# Roland_mem1.net
KiCad netlist of a schematic drawn in EAGLE
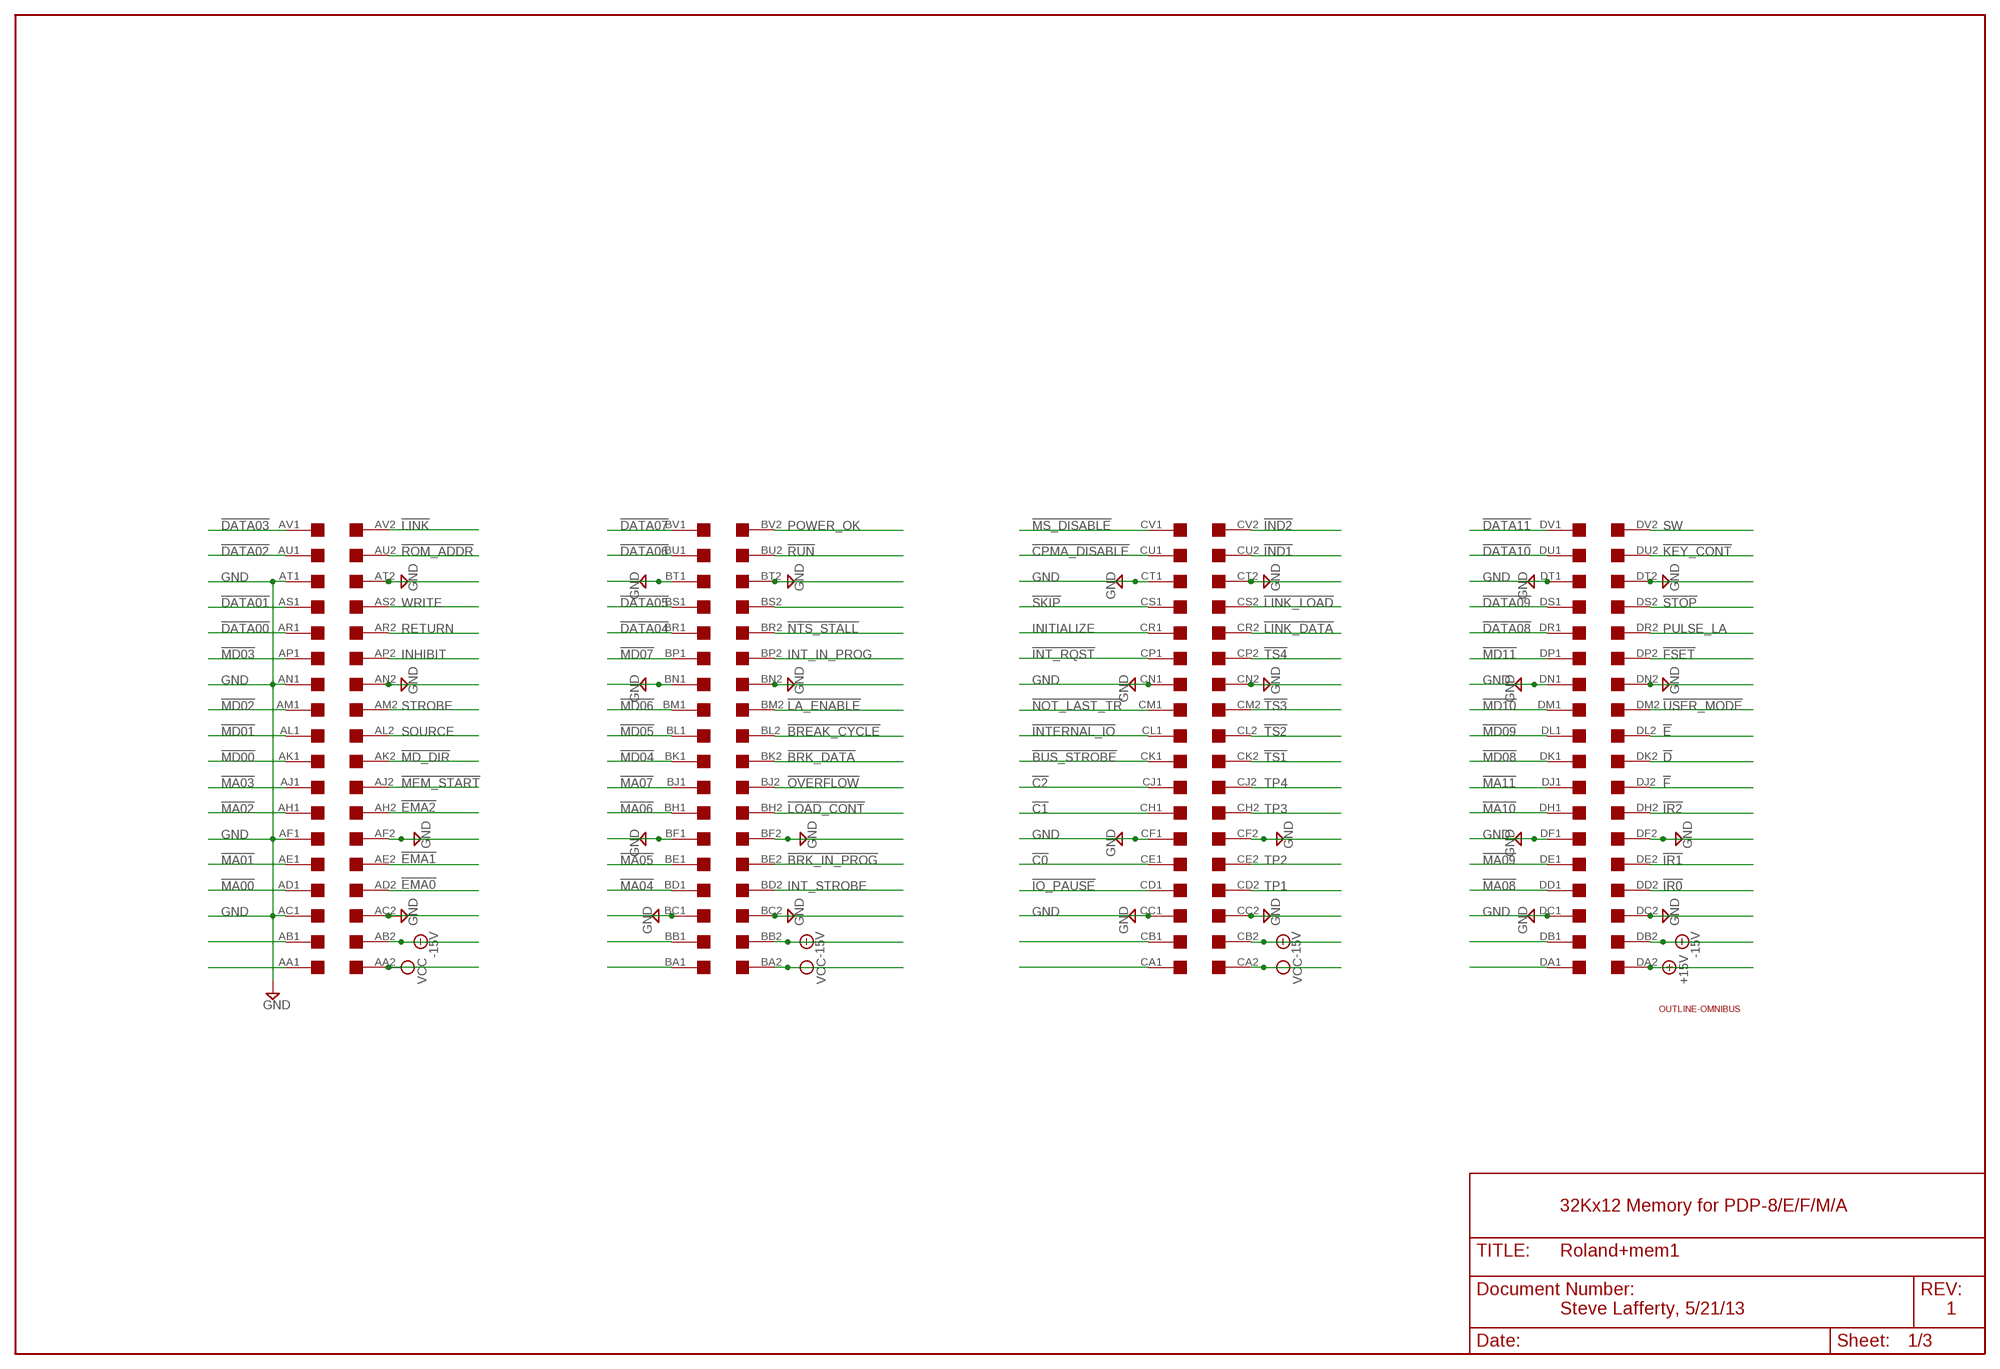
[diagram p0: schematic, sheet 1]
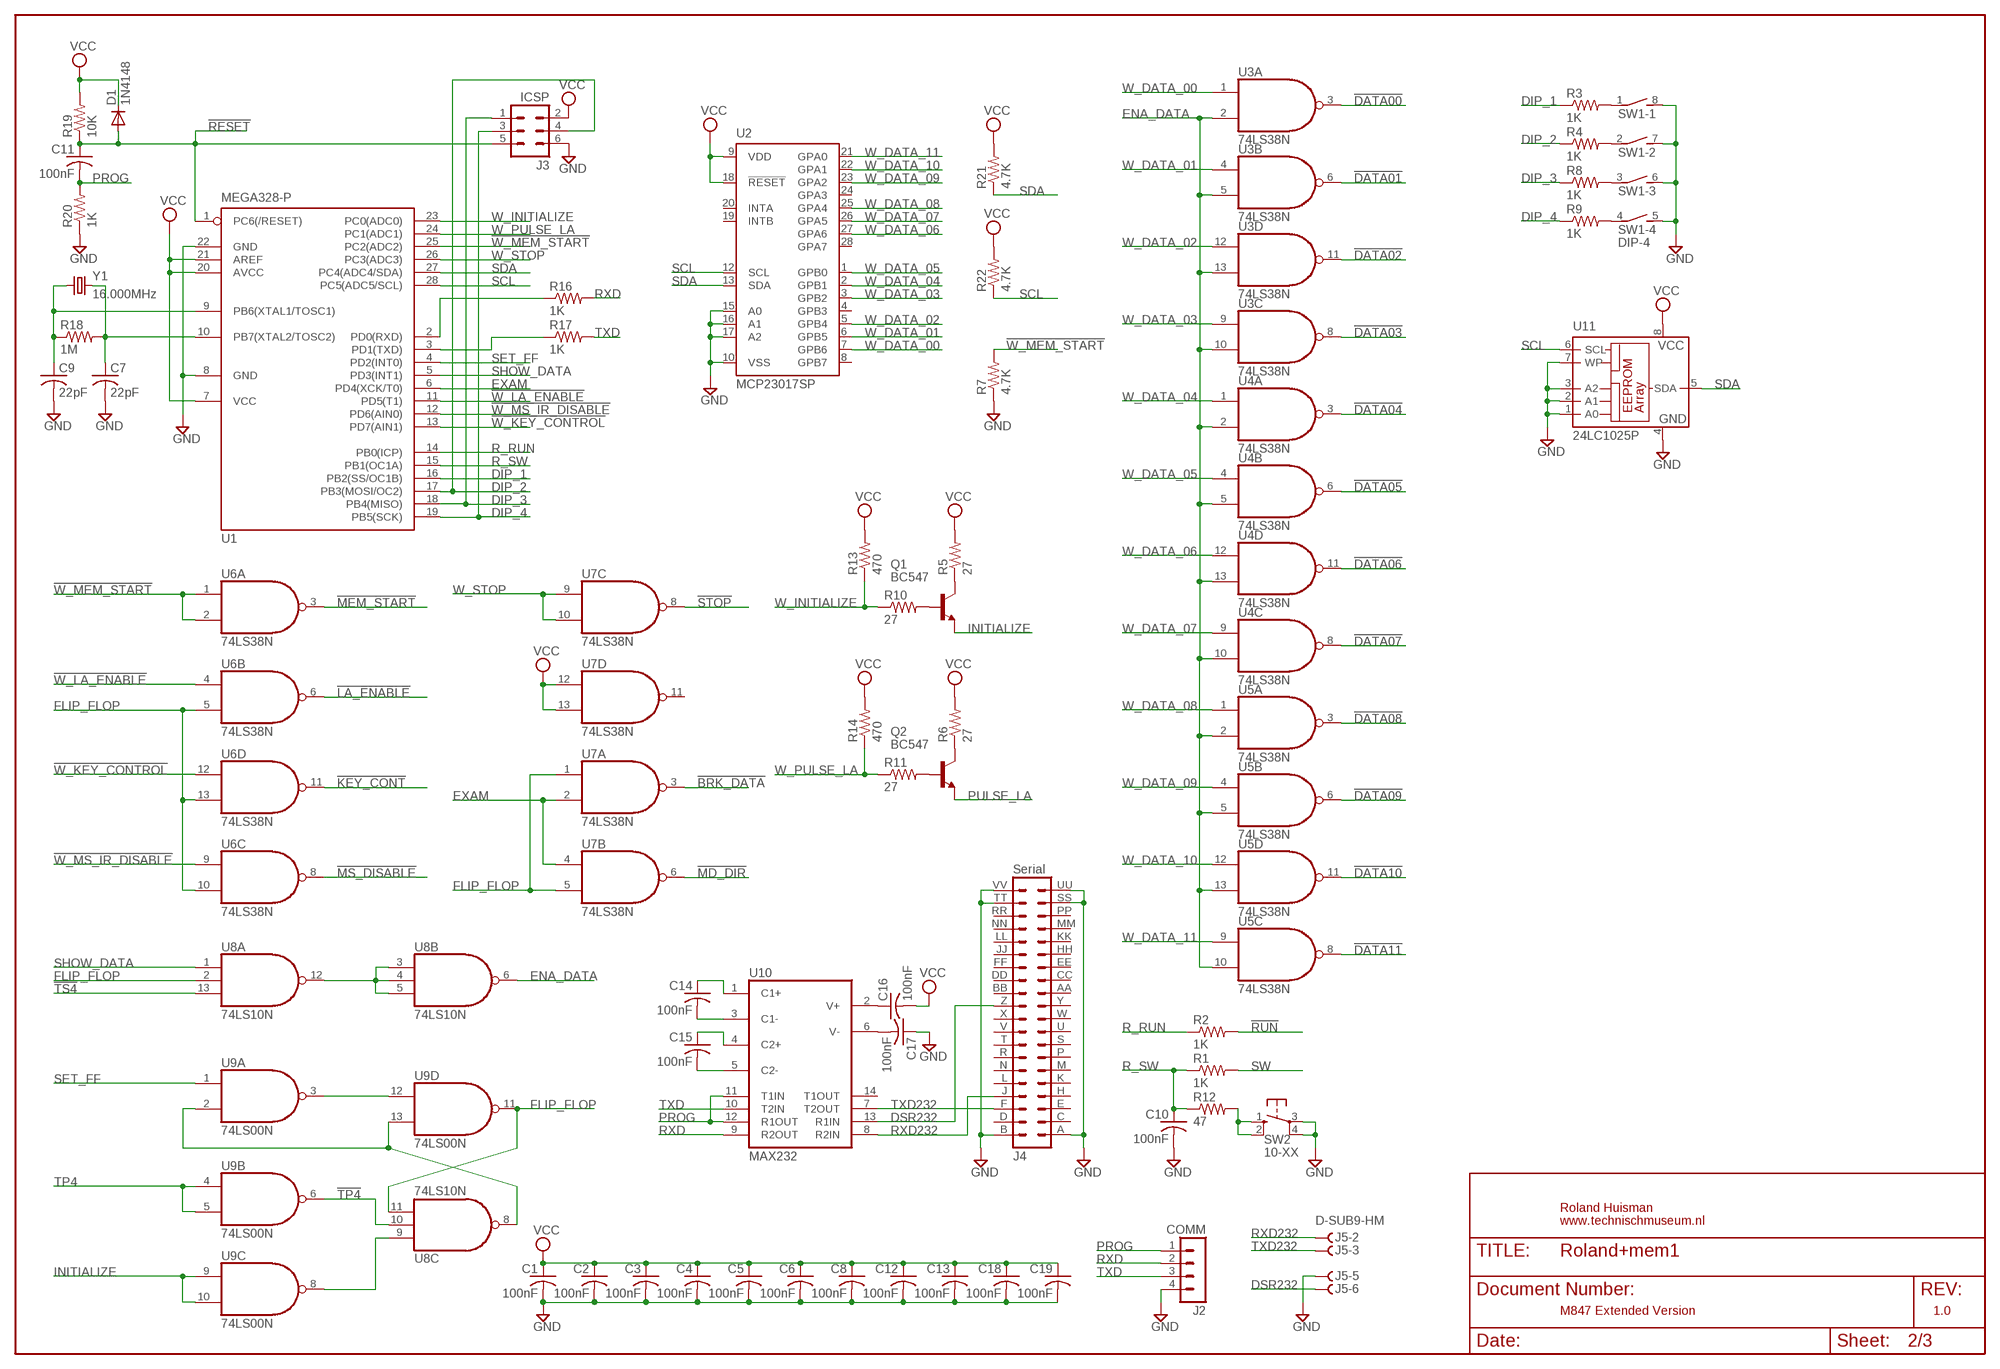
[diagram p1: schematic, sheet 2]
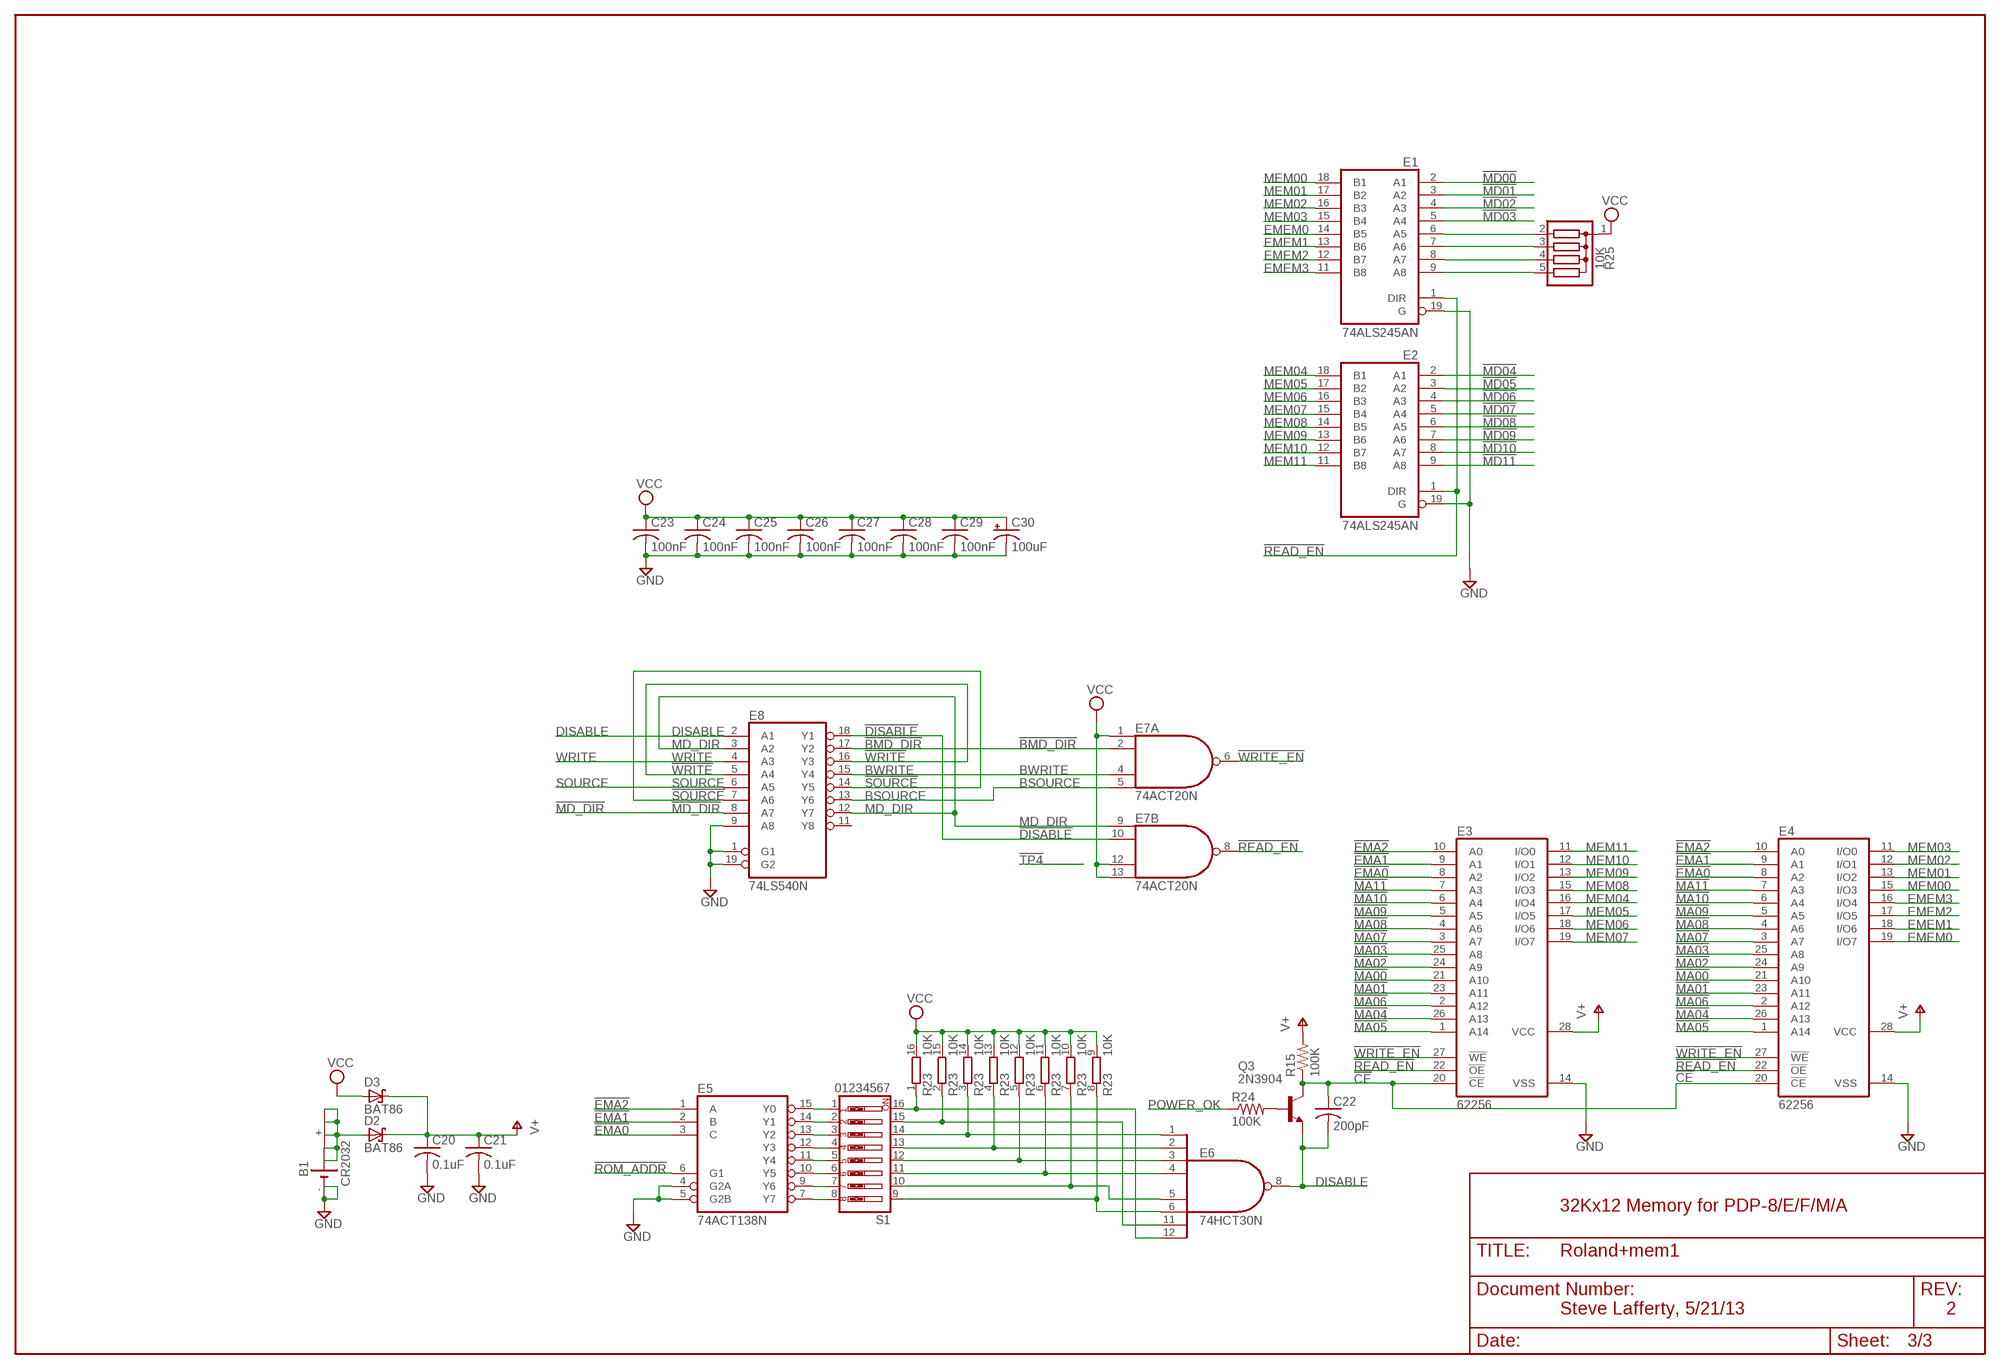
[diagram p2: schematic, sheet 3]

(export (version "E")
  (design (tool "Eeschema 10.0.6"))
  (components
    (comp (ref "B1")
      (value "CR2032")
      (footprint "eagle-import:B2430UNI")
      (libsource (lib "eagle-import") (part "B2430UNI"))
    )
    (comp (ref "C20")
      (value "0.1uF")
      (footprint "eagle-import:C050-025X075")
      (libsource (lib "eagle-import") (part "C-US050-025X075"))
    )
    (comp (ref "C21")
      (value "0.1uF")
      (footprint "eagle-import:C050-025X075")
      (libsource (lib "eagle-import") (part "C-US050-025X075"))
    )
    (comp (ref "C22")
      (value "200pF")
      (footprint "eagle-import:C050-025X075")
      (libsource (lib "eagle-import") (part "C-US050-025X075"))
    )
    (comp (ref "C23")
      (value "100nF")
      (footprint "eagle-import:C050-025X075")
      (libsource (lib "eagle-import") (part "C-US050-025X075"))
    )
    (comp (ref "C24")
      (value "100nF")
      (footprint "eagle-import:C050-025X075")
      (libsource (lib "eagle-import") (part "C-US050-025X075"))
    )
    (comp (ref "C25")
      (value "100nF")
      (footprint "eagle-import:C050-025X075")
      (libsource (lib "eagle-import") (part "C-US050-025X075"))
    )
    (comp (ref "C26")
      (value "100nF")
      (footprint "eagle-import:C050-025X075")
      (libsource (lib "eagle-import") (part "C-US050-025X075"))
    )
    (comp (ref "C27")
      (value "100nF")
      (footprint "eagle-import:C050-025X075")
      (libsource (lib "eagle-import") (part "C-US050-025X075"))
    )
    (comp (ref "C28")
      (value "100nF")
      (footprint "eagle-import:C050-025X075")
      (libsource (lib "eagle-import") (part "C-US050-025X075"))
    )
    (comp (ref "C29")
      (value "100nF")
      (footprint "eagle-import:C050-025X075")
      (libsource (lib "eagle-import") (part "C-US050-025X075"))
    )
    (comp (ref "C30")
      (value "100uF")
      (footprint "eagle-import:E12-8")
      (libsource (lib "eagle-import") (part "CPOL-USE20-8AXIAL"))
    )
    (comp (ref "D2")
      (value "BAT86")
      (footprint "eagle-import:DO35-10")
      (libsource (lib "eagle-import") (part "BAT19"))
    )
    (comp (ref "D3")
      (value "BAT86")
      (footprint "eagle-import:DO35-10")
      (libsource (lib "eagle-import") (part "BAT19"))
    )
    (comp (ref "E1")
      (value "74ALS245AN")
      (footprint "eagle-import:DIL20")
      (libsource (lib "eagle-import") (part "74245NLS"))
    )
    (comp (ref "E2")
      (value "74ALS245AN")
      (footprint "eagle-import:DIL20")
      (libsource (lib "eagle-import") (part "74245NLS"))
    )
    (comp (ref "E3")
      (value "62256")
      (footprint "eagle-import:DIL28-6")
      (libsource (lib "eagle-import") (part "58C256P"))
    )
    (comp (ref "E4")
      (value "62256")
      (footprint "eagle-import:DIL28-6")
      (libsource (lib "eagle-import") (part "58C256P"))
    )
    (comp (ref "E5")
      (value "74ACT138N")
      (footprint "eagle-import:DIL16")
      (libsource (lib "eagle-import") (part "74138NLS"))
    )
    (comp (ref "E6")
      (value "74HCT30N")
      (footprint "eagle-import:DIL14")
      (libsource (lib "eagle-import") (part "7430NLS"))
    )
    (comp (ref "E7")
      (value "74ACT20N")
      (footprint "eagle-import:DIL14")
      (libsource (lib "eagle-import") (part "7420NLS"))
    )
    (comp (ref "E8")
      (value "74LS540N")
      (footprint "eagle-import:DIL20")
      (libsource (lib "eagle-import") (part "74540NLS"))
    )
    (comp (ref "Q3")
      (value "2N3904")
      (footprint "eagle-import:TO92")
      (libsource (lib "eagle-import") (part "2N3904"))
    )
    (comp (ref "R15")
      (value "100K")
      (footprint "eagle-import:0207_10")
      (libsource (lib "eagle-import") (part "R-US_0207/10"))
    )
    (comp (ref "R23")
      (value "10K")
      (footprint "eagle-import:DIL16")
      (libsource (lib "eagle-import") (part "8R-P"))
    )
    (comp (ref "R24")
      (value "100K")
      (footprint "eagle-import:0207_10")
      (libsource (lib "eagle-import") (part "R-US_0207/10"))
    )
    (comp (ref "R25")
      (value "10K")
      (footprint "eagle-import:SIL5")
      (libsource (lib "eagle-import") (part "G04R"))
    )
    (comp (ref "S1")
      (value "01234567")
      (footprint "eagle-import:EDG-08")
      (libsource (lib "eagle-import") (part "SW_DIP-8"))
    )
    (comp (ref "C1")
      (value "100nF")
      (footprint "eagle-import:C050-025X075")
      (libsource (lib "eagle-import") (part "C-US050-025X075"))
    )
    (comp (ref "C2")
      (value "100nF")
      (footprint "eagle-import:C050-025X075")
      (libsource (lib "eagle-import") (part "C-US050-025X075"))
    )
    (comp (ref "C3")
      (value "100nF")
      (footprint "eagle-import:C050-025X075")
      (libsource (lib "eagle-import") (part "C-US050-025X075"))
    )
    (comp (ref "C4")
      (value "100nF")
      (footprint "eagle-import:C050-025X075")
      (libsource (lib "eagle-import") (part "C-US050-025X075"))
    )
    (comp (ref "C5")
      (value "100nF")
      (footprint "eagle-import:C050-025X075")
      (libsource (lib "eagle-import") (part "C-US050-025X075"))
    )
    (comp (ref "C6")
      (value "100nF")
      (footprint "eagle-import:C050-025X075")
      (libsource (lib "eagle-import") (part "C-US050-025X075"))
    )
    (comp (ref "C7")
      (value "22pF")
      (footprint "eagle-import:C050-025X075")
      (libsource (lib "eagle-import") (part "C-US050-025X075"))
    )
    (comp (ref "C8")
      (value "100nF")
      (footprint "eagle-import:C050-025X075")
      (libsource (lib "eagle-import") (part "C-US050-025X075"))
    )
    (comp (ref "C9")
      (value "22pF")
      (footprint "eagle-import:C050-025X075")
      (libsource (lib "eagle-import") (part "C-US050-025X075"))
    )
    (comp (ref "C10")
      (value "100nF")
      (footprint "eagle-import:C050-025X075")
      (libsource (lib "eagle-import") (part "C-US050-025X075"))
    )
    (comp (ref "C11")
      (value "100nF")
      (footprint "eagle-import:C050-025X075")
      (libsource (lib "eagle-import") (part "C-US050-025X075"))
    )
    (comp (ref "C12")
      (value "100nF")
      (footprint "eagle-import:C050-025X075")
      (libsource (lib "eagle-import") (part "C-US050-025X075"))
    )
    (comp (ref "C13")
      (value "100nF")
      (footprint "eagle-import:C050-025X075")
      (libsource (lib "eagle-import") (part "C-US050-025X075"))
    )
    (comp (ref "C14")
      (value "100nF")
      (footprint "eagle-import:C050-025X075")
      (libsource (lib "eagle-import") (part "C-US050-025X075"))
    )
    (comp (ref "C15")
      (value "100nF")
      (footprint "eagle-import:C050-025X075")
      (libsource (lib "eagle-import") (part "C-US050-025X075"))
    )
    (comp (ref "C16")
      (value "100nF")
      (footprint "eagle-import:C050-025X075")
      (libsource (lib "eagle-import") (part "C-US050-025X075"))
    )
    (comp (ref "C17")
      (value "100nF")
      (footprint "eagle-import:C050-025X075")
      (libsource (lib "eagle-import") (part "C-US050-025X075"))
    )
    (comp (ref "C18")
      (value "100nF")
      (footprint "eagle-import:C050-025X075")
      (libsource (lib "eagle-import") (part "C-US050-025X075"))
    )
    (comp (ref "C19")
      (value "100nF")
      (footprint "eagle-import:C050-025X075")
      (libsource (lib "eagle-import") (part "C-US050-025X075"))
    )
    (comp (ref "D1")
      (value "1N4148")
      (footprint "eagle-import:DO35-10")
      (libsource (lib "eagle-import") (part "1N4148DO35-10"))
    )
    (comp (ref "J2")
      (value "COMM")
      (footprint "eagle-import:MA04-1")
      (libsource (lib "eagle-import") (part "MA04-1"))
    )
    (comp (ref "J3")
      (value "ICSP")
      (footprint "eagle-import:MA03-2")
      (libsource (lib "eagle-import") (part "MA03-2"))
    )
    (comp (ref "J4")
      (value "Serial")
      (footprint "eagle-import:DEC40PINH")
      (libsource (lib "eagle-import") (part "DEC40PINH"))
    )
    (comp (ref "J5")
      (value "D-SUB9-HM")
      (footprint "eagle-import:H5M09RA")
      (libsource (lib "eagle-import") (part "D-SUB9-H5M09RA"))
    )
    (comp (ref "Q1")
      (value "BC547")
      (footprint "eagle-import:TO5")
      (libsource (lib "eagle-import") (part "-NPN-TO5"))
    )
    (comp (ref "Q2")
      (value "BC547")
      (footprint "eagle-import:TO5")
      (libsource (lib "eagle-import") (part "-NPN-TO5"))
    )
    (comp (ref "R1")
      (value "1K")
      (footprint "eagle-import:0207_10")
      (libsource (lib "eagle-import") (part "R-US_0207/10"))
    )
    (comp (ref "R2")
      (value "1K")
      (footprint "eagle-import:0207_10")
      (libsource (lib "eagle-import") (part "R-US_0207/10"))
    )
    (comp (ref "R3")
      (value "1K")
      (footprint "eagle-import:0207_10")
      (libsource (lib "eagle-import") (part "R-US_0207/10"))
    )
    (comp (ref "R4")
      (value "1K")
      (footprint "eagle-import:0207_10")
      (libsource (lib "eagle-import") (part "R-US_0207/10"))
    )
    (comp (ref "R5")
      (value "27")
      (footprint "eagle-import:0207_10")
      (libsource (lib "eagle-import") (part "R-US_0207/10"))
    )
    (comp (ref "R6")
      (value "27")
      (footprint "eagle-import:0207_10")
      (libsource (lib "eagle-import") (part "R-US_0207/10"))
    )
    (comp (ref "R7")
      (value "4.7K")
      (footprint "eagle-import:0207_10")
      (libsource (lib "eagle-import") (part "R-US_0207/10"))
    )
    (comp (ref "R8")
      (value "1K")
      (footprint "eagle-import:0207_10")
      (libsource (lib "eagle-import") (part "R-US_0207/10"))
    )
    (comp (ref "R9")
      (value "1K")
      (footprint "eagle-import:0207_10")
      (libsource (lib "eagle-import") (part "R-US_0207/10"))
    )
    (comp (ref "R10")
      (value "27")
      (footprint "eagle-import:0207_10")
      (libsource (lib "eagle-import") (part "R-US_0207/10"))
    )
    (comp (ref "R11")
      (value "27")
      (footprint "eagle-import:0207_10")
      (libsource (lib "eagle-import") (part "R-US_0207/10"))
    )
    (comp (ref "R12")
      (value "47")
      (footprint "eagle-import:0207_10")
      (libsource (lib "eagle-import") (part "R-US_0207/10"))
    )
    (comp (ref "R13")
      (value "470")
      (footprint "eagle-import:0207_10")
      (libsource (lib "eagle-import") (part "R-US_0207/10"))
    )
    (comp (ref "R14")
      (value "470")
      (footprint "eagle-import:0207_10")
      (libsource (lib "eagle-import") (part "R-US_0207/10"))
    )
    (comp (ref "R16")
      (value "1K")
      (footprint "eagle-import:0207_10")
      (libsource (lib "eagle-import") (part "R-US_0207/10"))
    )
    (comp (ref "R17")
      (value "1K")
      (footprint "eagle-import:0207_10")
      (libsource (lib "eagle-import") (part "R-US_0207/10"))
    )
    (comp (ref "R18")
      (value "1M")
      (footprint "eagle-import:0207_10")
      (libsource (lib "eagle-import") (part "R-US_0207/10"))
    )
    (comp (ref "R19")
      (value "10K")
      (footprint "eagle-import:0207_10")
      (libsource (lib "eagle-import") (part "R-US_0207/10"))
    )
    (comp (ref "R20")
      (value "1K")
      (footprint "eagle-import:0207_10")
      (libsource (lib "eagle-import") (part "R-US_0207/10"))
    )
    (comp (ref "R21")
      (value "4.7K")
      (footprint "eagle-import:0207_10")
      (libsource (lib "eagle-import") (part "R-US_0207/10"))
    )
    (comp (ref "R22")
      (value "4.7K")
      (footprint "eagle-import:0207_10")
      (libsource (lib "eagle-import") (part "R-US_0207/10"))
    )
    (comp (ref "SW1")
      (value "DIP-4")
      (footprint "eagle-import:DIP04S")
      (libsource (lib "eagle-import") (part "DIP04S"))
    )
    (comp (ref "SW2")
      (value "10-XX")
      (footprint "eagle-import:B3F-10XX")
      (fields (field (name "MPN") "B3F-1000"))
      (libsource (lib "eagle-import") (part "10-XX"))
    )
    (comp (ref "U1")
      (value "MEGA328-P")
      (footprint "eagle-import:DIL28-3")
      (libsource (lib "eagle-import") (part "MEGA8-P"))
    )
    (comp (ref "U2")
      (value "MCP23017SP")
      (footprint "eagle-import:DIL28-3")
      (fields (field (name "MF") "MICROCHIP") (field (name "MPN") "MCP23017-E/SP"))
      (libsource (lib "eagle-import") (part "MCP23017SP"))
    )
    (comp (ref "U3")
      (value "74LS38N")
      (footprint "eagle-import:DIL14")
      (libsource (lib "eagle-import") (part "7438NLS"))
    )
    (comp (ref "U4")
      (value "74LS38N")
      (footprint "eagle-import:DIL14")
      (libsource (lib "eagle-import") (part "7438NLS"))
    )
    (comp (ref "U5")
      (value "74LS38N")
      (footprint "eagle-import:DIL14")
      (libsource (lib "eagle-import") (part "7438NLS"))
    )
    (comp (ref "U6")
      (value "74LS38N")
      (footprint "eagle-import:DIL14")
      (libsource (lib "eagle-import") (part "7438NLS"))
    )
    (comp (ref "U7")
      (value "74LS38N")
      (footprint "eagle-import:DIL14")
      (libsource (lib "eagle-import") (part "7438NLS"))
    )
    (comp (ref "U8")
      (value "74LS10N")
      (footprint "eagle-import:DIL14")
      (libsource (lib "eagle-import") (part "7410NLS"))
    )
    (comp (ref "U9")
      (value "74LS00N")
      (footprint "eagle-import:DIL14")
      (libsource (lib "eagle-import") (part "7400NLS"))
    )
    (comp (ref "U10")
      (value "MAX232")
      (footprint "eagle-import:DIL16")
      (fields (field (name "MF") "MAXIM") (field (name "MPN") "MAX232ACPE+"))
      (libsource (lib "eagle-import") (part "MAX232"))
    )
    (comp (ref "U11")
      (value "24LC1025P")
      (footprint "eagle-import:DIL8")
      (fields (field (name "MF") "MICROCHIP") (field (name "MPN") "24LC025-I/P"))
      (libsource (lib "eagle-import") (part "24PLC025"))
    )
    (comp (ref "Y1")
      (value "16.000MHz")
      (footprint "eagle-import:HC49U-H")
      (libsource (lib "eagle-import") (part "CRYSTALHC49U-H"))
    )
    (comp (ref "J1")
      (value "EDGE")
      (footprint "eagle-import:EDGE-CON8")
      (libsource (lib "eagle-import") (part "QUAD"))
    )
    (comp (ref "U$1")
      (value "OUTLINE-OMNIBUS")
      (footprint "eagle-import:OMNIBUS")
      (libsource (lib "eagle-import") (part "OUTLINE-OMNIBUS"))
    )
  )
  (nets
    (net (code "1") (name "+15V") (class "Default")
      (node (ref "J1") (pin "DA2") (pinfunction "1_DA2") (pintype "bidirectional"))
    )
    (net (code "2") (name "-15V") (class "Default")
      (node (ref "J1") (pin "AB2") (pinfunction "1_AB2") (pintype "bidirectional"))
      (node (ref "J1") (pin "BB2") (pinfunction "1_BB2") (pintype "bidirectional"))
      (node (ref "J1") (pin "CB2") (pinfunction "1_CB2") (pintype "bidirectional"))
      (node (ref "J1") (pin "DB2") (pinfunction "1_DB2") (pintype "bidirectional"))
    )
    (net (code "3") (name "BSOURCE") (class "Default")
      (node (ref "E7") (pin "5") (pinfunction "I3_5") (pintype "input"))
      (node (ref "E8") (pin "13") (pinfunction "Y6_13") (pintype "tri_state"))
    )
    (net (code "4") (name "BWRITE") (class "Default")
      (node (ref "E7") (pin "4") (pinfunction "I2_4") (pintype "input"))
      (node (ref "E8") (pin "15") (pinfunction "Y4_15") (pintype "tri_state"))
    )
    (net (code "5") (name "DIP_1") (class "Default")
      (node (ref "R3") (pin "1") (pinfunction "1_1") (pintype "passive"))
      (node (ref "U1") (pin "16") (pinfunction "PB2(SS/OC1B)_16") (pintype "bidirectional"))
    )
    (net (code "6") (name "DIP_2") (class "Default")
      (node (ref "J3") (pin "4") (pinfunction "4_4") (pintype "passive"))
      (node (ref "R4") (pin "1") (pinfunction "1_1") (pintype "passive"))
      (node (ref "U1") (pin "17") (pinfunction "PB3(MOSI/OC2)_17") (pintype "bidirectional"))
    )
    (net (code "7") (name "DIP_3") (class "Default")
      (node (ref "J3") (pin "1") (pinfunction "1_1") (pintype "passive"))
      (node (ref "R8") (pin "1") (pinfunction "1_1") (pintype "passive"))
      (node (ref "U1") (pin "18") (pinfunction "PB4(MISO)_18") (pintype "bidirectional"))
    )
    (net (code "8") (name "DIP_4") (class "Default")
      (node (ref "J3") (pin "3") (pinfunction "3_3") (pintype "passive"))
      (node (ref "R9") (pin "1") (pinfunction "1_1") (pintype "passive"))
      (node (ref "U1") (pin "19") (pinfunction "PB5(SCK)_19") (pintype "bidirectional"))
    )
    (net (code "9") (name "DISABLE") (class "Default")
      (node (ref "C22") (pin "2") (pinfunction "2_2") (pintype "passive"))
      (node (ref "E6") (pin "8") (pinfunction "O_8") (pintype "output"))
      (node (ref "E8") (pin "2") (pinfunction "A1_2") (pintype "input"))
      (node (ref "Q3") (pin "3") (pinfunction "E_3") (pintype "passive"))
    )
    (net (code "10") (name "DSR232") (class "Default")
      (node (ref "J4") (pin "Z") (pinfunction "22_Z") (pintype "bidirectional"))
      (node (ref "J5") (pin "6") (pinfunction "F_6") (pintype "passive"))
      (node (ref "U10") (pin "13") (pinfunction "R1IN_13") (pintype "input"))
    )
    (net (code "11") (name "EMEM0") (class "Default")
      (node (ref "E1") (pin "14") (pinfunction "B5_14") (pintype "bidirectional"))
      (node (ref "E4") (pin "19") (pinfunction "I/O7_19") (pintype "tri_state"))
    )
    (net (code "12") (name "EMEM1") (class "Default")
      (node (ref "E1") (pin "13") (pinfunction "B6_13") (pintype "bidirectional"))
      (node (ref "E4") (pin "18") (pinfunction "I/O6_18") (pintype "tri_state"))
    )
    (net (code "13") (name "EMEM2") (class "Default")
      (node (ref "E1") (pin "12") (pinfunction "B7_12") (pintype "bidirectional"))
      (node (ref "E4") (pin "17") (pinfunction "I/O5_17") (pintype "tri_state"))
    )
    (net (code "14") (name "EMEM3") (class "Default")
      (node (ref "E1") (pin "11") (pinfunction "B8_11") (pintype "bidirectional"))
      (node (ref "E4") (pin "16") (pinfunction "I/O4_16") (pintype "tri_state"))
    )
    (net (code "15") (name "ENA_DATA") (class "Default")
      (node (ref "U3") (pin "10") (pinfunction "I1_10") (pintype "input"))
      (node (ref "U3") (pin "13") (pinfunction "I1_13") (pintype "input"))
      (node (ref "U3") (pin "2") (pinfunction "I1_2") (pintype "input"))
      (node (ref "U3") (pin "5") (pinfunction "I1_5") (pintype "input"))
      (node (ref "U4") (pin "10") (pinfunction "I1_10") (pintype "input"))
      (node (ref "U4") (pin "13") (pinfunction "I1_13") (pintype "input"))
      (node (ref "U4") (pin "2") (pinfunction "I1_2") (pintype "input"))
      (node (ref "U4") (pin "5") (pinfunction "I1_5") (pintype "input"))
      (node (ref "U5") (pin "10") (pinfunction "I1_10") (pintype "input"))
      (node (ref "U5") (pin "13") (pinfunction "I1_13") (pintype "input"))
      (node (ref "U5") (pin "2") (pinfunction "I1_2") (pintype "input"))
      (node (ref "U5") (pin "5") (pinfunction "I1_5") (pintype "input"))
      (node (ref "U8") (pin "6") (pinfunction "O_6") (pintype "output"))
    )
    (net (code "16") (name "EXAM") (class "Default")
      (node (ref "U1") (pin "6") (pinfunction "PD4(XCK/T0)_6") (pintype "bidirectional"))
      (node (ref "U7") (pin "2") (pinfunction "I1_2") (pintype "input"))
      (node (ref "U7") (pin "4") (pinfunction "I0_4") (pintype "input"))
    )
    (net (code "17") (name "FLIP_FLOP") (class "Default")
      (node (ref "U6") (pin "10") (pinfunction "I1_10") (pintype "input"))
      (node (ref "U6") (pin "13") (pinfunction "I1_13") (pintype "input"))
      (node (ref "U6") (pin "5") (pinfunction "I1_5") (pintype "input"))
      (node (ref "U7") (pin "1") (pinfunction "I0_1") (pintype "input"))
      (node (ref "U7") (pin "5") (pinfunction "I1_5") (pintype "input"))
      (node (ref "U8") (pin "11") (pinfunction "I2_11") (pintype "input"))
      (node (ref "U8") (pin "2") (pinfunction "I1_2") (pintype "input"))
      (node (ref "U9") (pin "11") (pinfunction "O_11") (pintype "output"))
    )
    (net (code "18") (name "GND") (class "Default")
      (node (ref "B1") (pin "-") (pinfunction "-_-") (pintype "passive"))
      (node (ref "B1") (pin "-@1") (pinfunction "-_-@1") (pintype "passive"))
      (node (ref "C1") (pin "2") (pinfunction "2_2") (pintype "passive"))
      (node (ref "C10") (pin "2") (pinfunction "2_2") (pintype "passive"))
      (node (ref "C12") (pin "2") (pinfunction "2_2") (pintype "passive"))
      (node (ref "C13") (pin "2") (pinfunction "2_2") (pintype "passive"))
      (node (ref "C17") (pin "1") (pinfunction "1_1") (pintype "passive"))
      (node (ref "C18") (pin "2") (pinfunction "2_2") (pintype "passive"))
      (node (ref "C19") (pin "2") (pinfunction "2_2") (pintype "passive"))
      (node (ref "C2") (pin "2") (pinfunction "2_2") (pintype "passive"))
      (node (ref "C20") (pin "2") (pinfunction "2_2") (pintype "passive"))
      (node (ref "C21") (pin "2") (pinfunction "2_2") (pintype "passive"))
      (node (ref "C23") (pin "2") (pinfunction "2_2") (pintype "passive"))
      (node (ref "C24") (pin "2") (pinfunction "2_2") (pintype "passive"))
      (node (ref "C25") (pin "2") (pinfunction "2_2") (pintype "passive"))
      (node (ref "C26") (pin "2") (pinfunction "2_2") (pintype "passive"))
      (node (ref "C27") (pin "2") (pinfunction "2_2") (pintype "passive"))
      (node (ref "C28") (pin "2") (pinfunction "2_2") (pintype "passive"))
      (node (ref "C29") (pin "2") (pinfunction "2_2") (pintype "passive"))
      (node (ref "C3") (pin "2") (pinfunction "2_2") (pintype "passive"))
      (node (ref "C30") (pin "-") (pinfunction "-_-") (pintype "passive"))
      (node (ref "C4") (pin "2") (pinfunction "2_2") (pintype "passive"))
      (node (ref "C5") (pin "2") (pinfunction "2_2") (pintype "passive"))
      (node (ref "C6") (pin "2") (pinfunction "2_2") (pintype "passive"))
      (node (ref "C7") (pin "2") (pinfunction "2_2") (pintype "passive"))
      (node (ref "C8") (pin "2") (pinfunction "2_2") (pintype "passive"))
      (node (ref "C9") (pin "2") (pinfunction "2_2") (pintype "passive"))
      (node (ref "E1") (pin "19") (pinfunction "G_19") (pintype "input"))
      (node (ref "E2") (pin "19") (pinfunction "G_19") (pintype "input"))
      (node (ref "E3") (pin "14") (pinfunction "VSS_14") (pintype "power_in"))
      (node (ref "E4") (pin "14") (pinfunction "VSS_14") (pintype "power_in"))
      (node (ref "E5") (pin "4") (pinfunction "G2A_4") (pintype "input"))
      (node (ref "E5") (pin "5") (pinfunction "G2B_5") (pintype "input"))
      (node (ref "E8") (pin "1") (pinfunction "G1_1") (pintype "input"))
      (node (ref "E8") (pin "19") (pinfunction "G2_19") (pintype "input"))
      (node (ref "E8") (pin "9") (pinfunction "A8_9") (pintype "input"))
      (node (ref "J1") (pin "AC1") (pinfunction "1_AC1") (pintype "bidirectional"))
      (node (ref "J1") (pin "AC2") (pinfunction "1_AC2") (pintype "bidirectional"))
      (node (ref "J1") (pin "AF1") (pinfunction "1_AF1") (pintype "bidirectional"))
      (node (ref "J1") (pin "AF2") (pinfunction "1_AF2") (pintype "bidirectional"))
      (node (ref "J1") (pin "AN1") (pinfunction "1_AN1") (pintype "bidirectional"))
      (node (ref "J1") (pin "AN2") (pinfunction "1_AN2") (pintype "bidirectional"))
      (node (ref "J1") (pin "AT1") (pinfunction "1_AT1") (pintype "bidirectional"))
      (node (ref "J1") (pin "AT2") (pinfunction "1_AT2") (pintype "bidirectional"))
      (node (ref "J1") (pin "BC1") (pinfunction "1_BC1") (pintype "bidirectional"))
      (node (ref "J1") (pin "BC2") (pinfunction "1_BC2") (pintype "bidirectional"))
      (node (ref "J1") (pin "BF1") (pinfunction "1_BF1") (pintype "bidirectional"))
      (node (ref "J1") (pin "BF2") (pinfunction "1_BF2") (pintype "bidirectional"))
      (node (ref "J1") (pin "BN1") (pinfunction "1_BN1") (pintype "bidirectional"))
      (node (ref "J1") (pin "BN2") (pinfunction "1_BN2") (pintype "bidirectional"))
      (node (ref "J1") (pin "BT1") (pinfunction "1_BT1") (pintype "bidirectional"))
      (node (ref "J1") (pin "BT2") (pinfunction "1_BT2") (pintype "bidirectional"))
      (node (ref "J1") (pin "CC1") (pinfunction "1_CC1") (pintype "bidirectional"))
      (node (ref "J1") (pin "CC2") (pinfunction "1_CC2") (pintype "bidirectional"))
      (node (ref "J1") (pin "CF1") (pinfunction "1_CF1") (pintype "bidirectional"))
      (node (ref "J1") (pin "CF2") (pinfunction "1_CF2") (pintype "bidirectional"))
      (node (ref "J1") (pin "CN1") (pinfunction "1_CN1") (pintype "bidirectional"))
      (node (ref "J1") (pin "CN2") (pinfunction "1_CN2") (pintype "bidirectional"))
      (node (ref "J1") (pin "CT1") (pinfunction "1_CT1") (pintype "bidirectional"))
      (node (ref "J1") (pin "CT2") (pinfunction "1_CT2") (pintype "bidirectional"))
      (node (ref "J1") (pin "DC1") (pinfunction "1_DC1") (pintype "bidirectional"))
      (node (ref "J1") (pin "DC2") (pinfunction "1_DC2") (pintype "bidirectional"))
      (node (ref "J1") (pin "DF1") (pinfunction "1_DF1") (pintype "bidirectional"))
      (node (ref "J1") (pin "DF2") (pinfunction "1_DF2") (pintype "bidirectional"))
      (node (ref "J1") (pin "DN1") (pinfunction "1_DN1") (pintype "bidirectional"))
      (node (ref "J1") (pin "DN2") (pinfunction "1_DN2") (pintype "bidirectional"))
      (node (ref "J1") (pin "DT1") (pinfunction "1_DT1") (pintype "bidirectional"))
      (node (ref "J1") (pin "DT2") (pinfunction "1_DT2") (pintype "bidirectional"))
      (node (ref "J2") (pin "4") (pinfunction "4_4") (pintype "passive"))
      (node (ref "J3") (pin "6") (pinfunction "6_6") (pintype "passive"))
      (node (ref "J4") (pin "A") (pinfunction "1_A") (pintype "bidirectional"))
      (node (ref "J4") (pin "B") (pinfunction "2_B") (pintype "bidirectional"))
      (node (ref "J4") (pin "SS") (pinfunction "37_SS") (pintype "bidirectional"))
      (node (ref "J4") (pin "TT") (pinfunction "38_TT") (pintype "bidirectional"))
      (node (ref "J4") (pin "UU") (pinfunction "39_UU") (pintype "bidirectional"))
      (node (ref "J4") (pin "VV") (pinfunction "40_VV") (pintype "bidirectional"))
      (node (ref "J5") (pin "5") (pinfunction "F_5") (pintype "passive"))
      (node (ref "R20") (pin "1") (pinfunction "1_1") (pintype "passive"))
      (node (ref "R7") (pin "1") (pinfunction "1_1") (pintype "passive"))
      (node (ref "SW1") (pin "5") (pinfunction "2_5") (pintype "passive"))
      (node (ref "SW1") (pin "6") (pinfunction "2_6") (pintype "passive"))
      (node (ref "SW1") (pin "7") (pinfunction "2_7") (pintype "passive"))
      (node (ref "SW1") (pin "8") (pinfunction "2_8") (pintype "passive"))
      (node (ref "SW2") (pin "3") (pinfunction "P_3") (pintype "passive"))
      (node (ref "SW2") (pin "4") (pinfunction "P1_4") (pintype "passive"))
      (node (ref "U1") (pin "22") (pinfunction "GND_22") (pintype "power_in"))
      (node (ref "U1") (pin "8") (pinfunction "GND_8") (pintype "power_in"))
      (node (ref "U11") (pin "1") (pinfunction "A0_1") (pintype "input"))
      (node (ref "U11") (pin "2") (pinfunction "A1_2") (pintype "input"))
      (node (ref "U11") (pin "3") (pinfunction "A2_3") (pintype "input"))
      (node (ref "U11") (pin "4") (pinfunction "GND_4") (pintype "power_in"))
      (node (ref "U11") (pin "7") (pinfunction "WP_7") (pintype "input"))
      (node (ref "U2") (pin "10") (pinfunction "VSS_10") (pintype "power_in"))
      (node (ref "U2") (pin "15") (pinfunction "A0_15") (pintype "input"))
      (node (ref "U2") (pin "16") (pinfunction "A1_16") (pintype "input"))
      (node (ref "U2") (pin "17") (pinfunction "A2_17") (pintype "input"))
    )
    (net (code "19") (name "INHIBIT") (class "Default")
      (node (ref "J1") (pin "AP2") (pinfunction "1_AP2") (pintype "bidirectional"))
    )
    (net (code "20") (name "INITIALIZE") (class "Default")
      (node (ref "J1") (pin "CR1") (pinfunction "1_CR1") (pintype "bidirectional"))
      (node (ref "Q1") (pin "1") (pinfunction "E_1") (pintype "passive"))
      (node (ref "U9") (pin "10") (pinfunction "I1_10") (pintype "input"))
      (node (ref "U9") (pin "9") (pinfunction "I0_9") (pintype "input"))
    )
    (net (code "21") (name "INT_IN_PROG") (class "Default")
      (node (ref "J1") (pin "BP2") (pinfunction "1_BP2") (pintype "bidirectional"))
    )
    (net (code "22") (name "INT_STROBE") (class "Default")
      (node (ref "J1") (pin "BD2") (pinfunction "1_BD2") (pintype "bidirectional"))
    )
    (net (code "23") (name "MD_DIR") (class "Default")
      (node (ref "E7") (pin "9") (pinfunction "I0_9") (pintype "input"))
      (node (ref "E8") (pin "12") (pinfunction "Y7_12") (pintype "tri_state"))
      (node (ref "E8") (pin "3") (pinfunction "A2_3") (pintype "input"))
    )
    (net (code "24") (name "MEM00") (class "Default")
      (node (ref "E1") (pin "18") (pinfunction "B1_18") (pintype "bidirectional"))
      (node (ref "E4") (pin "15") (pinfunction "I/O3_15") (pintype "tri_state"))
    )
    (net (code "25") (name "MEM01") (class "Default")
      (node (ref "E1") (pin "17") (pinfunction "B2_17") (pintype "bidirectional"))
      (node (ref "E4") (pin "13") (pinfunction "I/O2_13") (pintype "tri_state"))
    )
    (net (code "26") (name "MEM02") (class "Default")
      (node (ref "E1") (pin "16") (pinfunction "B3_16") (pintype "bidirectional"))
      (node (ref "E4") (pin "12") (pinfunction "I/O1_12") (pintype "tri_state"))
    )
    (net (code "27") (name "MEM03") (class "Default")
      (node (ref "E1") (pin "15") (pinfunction "B4_15") (pintype "bidirectional"))
      (node (ref "E4") (pin "11") (pinfunction "I/O0_11") (pintype "tri_state"))
    )
    (net (code "28") (name "MEM04") (class "Default")
      (node (ref "E2") (pin "18") (pinfunction "B1_18") (pintype "bidirectional"))
      (node (ref "E3") (pin "16") (pinfunction "I/O4_16") (pintype "tri_state"))
    )
    (net (code "29") (name "MEM05") (class "Default")
      (node (ref "E2") (pin "17") (pinfunction "B2_17") (pintype "bidirectional"))
      (node (ref "E3") (pin "17") (pinfunction "I/O5_17") (pintype "tri_state"))
    )
    (net (code "30") (name "MEM06") (class "Default")
      (node (ref "E2") (pin "16") (pinfunction "B3_16") (pintype "bidirectional"))
      (node (ref "E3") (pin "18") (pinfunction "I/O6_18") (pintype "tri_state"))
    )
    (net (code "31") (name "MEM07") (class "Default")
      (node (ref "E2") (pin "15") (pinfunction "B4_15") (pintype "bidirectional"))
      (node (ref "E3") (pin "19") (pinfunction "I/O7_19") (pintype "tri_state"))
    )
    (net (code "32") (name "MEM08") (class "Default")
      (node (ref "E2") (pin "14") (pinfunction "B5_14") (pintype "bidirectional"))
      (node (ref "E3") (pin "15") (pinfunction "I/O3_15") (pintype "tri_state"))
    )
    (net (code "33") (name "MEM09") (class "Default")
      (node (ref "E2") (pin "13") (pinfunction "B6_13") (pintype "bidirectional"))
      (node (ref "E3") (pin "13") (pinfunction "I/O2_13") (pintype "tri_state"))
    )
    (net (code "34") (name "MEM10") (class "Default")
      (node (ref "E2") (pin "12") (pinfunction "B7_12") (pintype "bidirectional"))
      (node (ref "E3") (pin "12") (pinfunction "I/O1_12") (pintype "tri_state"))
    )
    (net (code "35") (name "MEM11") (class "Default")
      (node (ref "E2") (pin "11") (pinfunction "B8_11") (pintype "bidirectional"))
      (node (ref "E3") (pin "11") (pinfunction "I/O0_11") (pintype "tri_state"))
    )
    (net (code "36") (name "Net-(B1-+-Pad+@1)") (class "Default")
      (node (ref "B1") (pin "+") (pinfunction "+_+") (pintype "passive"))
      (node (ref "B1") (pin "+@1") (pinfunction "+_+@1") (pintype "passive"))
      (node (ref "B1") (pin "+@2") (pinfunction "+_+@2") (pintype "passive"))
      (node (ref "B1") (pin "+@3") (pinfunction "+_+@3") (pintype "passive"))
      (node (ref "B1") (pin "+@4") (pinfunction "+_+@4") (pintype "passive"))
      (node (ref "D2") (pin "A") (pinfunction "A_A") (pintype "passive"))
    )
    (net (code "37") (name "Net-(E1A-A5)") (class "Default")
      (node (ref "E1") (pin "6") (pinfunction "A5_6") (pintype "bidirectional"))
      (node (ref "R25") (pin "2") (pinfunction "2_2") (pintype "passive"))
    )
    (net (code "38") (name "Net-(E1A-A6)") (class "Default")
      (node (ref "E1") (pin "7") (pinfunction "A6_7") (pintype "bidirectional"))
      (node (ref "R25") (pin "3") (pinfunction "3_3") (pintype "passive"))
    )
    (net (code "39") (name "Net-(E1A-A7)") (class "Default")
      (node (ref "E1") (pin "8") (pinfunction "A7_8") (pintype "bidirectional"))
      (node (ref "R25") (pin "4") (pinfunction "4_4") (pintype "passive"))
    )
    (net (code "40") (name "Net-(E1A-A8)") (class "Default")
      (node (ref "E1") (pin "9") (pinfunction "A8_9") (pintype "bidirectional"))
      (node (ref "R25") (pin "5") (pinfunction "5_5") (pintype "passive"))
    )
    (net (code "41") (name "Net-(E5A-Y0)") (class "Default")
      (node (ref "E5") (pin "15") (pinfunction "Y0_15") (pintype "output"))
      (node (ref "S1") (pin "1") (pinfunction "1_1") (pintype "passive"))
    )
    (net (code "42") (name "Net-(E5A-Y1)") (class "Default")
      (node (ref "E5") (pin "14") (pinfunction "Y1_14") (pintype "output"))
      (node (ref "S1") (pin "2") (pinfunction "2_2") (pintype "passive"))
    )
    (net (code "43") (name "Net-(E5A-Y2)") (class "Default")
      (node (ref "E5") (pin "13") (pinfunction "Y2_13") (pintype "output"))
      (node (ref "S1") (pin "3") (pinfunction "3_3") (pintype "passive"))
    )
    (net (code "44") (name "Net-(E5A-Y3)") (class "Default")
      (node (ref "E5") (pin "12") (pinfunction "Y3_12") (pintype "output"))
      (node (ref "S1") (pin "4") (pinfunction "4_4") (pintype "passive"))
    )
    (net (code "45") (name "Net-(E5A-Y4)") (class "Default")
      (node (ref "E5") (pin "11") (pinfunction "Y4_11") (pintype "output"))
      (node (ref "S1") (pin "5") (pinfunction "5_5") (pintype "passive"))
    )
    (net (code "46") (name "Net-(E5A-Y5)") (class "Default")
      (node (ref "E5") (pin "10") (pinfunction "Y5_10") (pintype "output"))
      (node (ref "S1") (pin "6") (pinfunction "6_6") (pintype "passive"))
    )
    (net (code "47") (name "Net-(E5A-Y6)") (class "Default")
      (node (ref "E5") (pin "9") (pinfunction "Y6_9") (pintype "output"))
      (node (ref "S1") (pin "7") (pinfunction "7_7") (pintype "passive"))
    )
    (net (code "48") (name "Net-(E5A-Y7)") (class "Default")
      (node (ref "E5") (pin "7") (pinfunction "Y7_7") (pintype "output"))
      (node (ref "S1") (pin "8") (pinfunction "8_8") (pintype "passive"))
    )
    (net (code "49") (name "Net-(E6A-I0)") (class "Default")
      (node (ref "E6") (pin "1") (pinfunction "I0_1") (pintype "input"))
      (node (ref "R23") (pin "3") (pinfunction "1_3") (pintype "passive"))
      (node (ref "S1") (pin "14") (pinfunction "14_14") (pintype "passive"))
    )
    (net (code "50") (name "Net-(E6A-I1)") (class "Default")
      (node (ref "E6") (pin "2") (pinfunction "I1_2") (pintype "input"))
      (node (ref "R23") (pin "4") (pinfunction "1_4") (pintype "passive"))
      (node (ref "S1") (pin "13") (pinfunction "13_13") (pintype "passive"))
    )
    (net (code "51") (name "Net-(E6A-I2)") (class "Default")
      (node (ref "E6") (pin "3") (pinfunction "I2_3") (pintype "input"))
      (node (ref "R23") (pin "5") (pinfunction "1_5") (pintype "passive"))
      (node (ref "S1") (pin "12") (pinfunction "12_12") (pintype "passive"))
    )
    (net (code "52") (name "Net-(E6A-I3)") (class "Default")
      (node (ref "E6") (pin "4") (pinfunction "I3_4") (pintype "input"))
      (node (ref "R23") (pin "6") (pinfunction "1_6") (pintype "passive"))
      (node (ref "S1") (pin "11") (pinfunction "11_11") (pintype "passive"))
    )
    (net (code "53") (name "Net-(E6A-I4)") (class "Default")
      (node (ref "E6") (pin "5") (pinfunction "I4_5") (pintype "input"))
      (node (ref "R23") (pin "7") (pinfunction "1_7") (pintype "passive"))
      (node (ref "S1") (pin "10") (pinfunction "10_10") (pintype "passive"))
    )
    (net (code "54") (name "Net-(E6A-I5)") (class "Default")
      (node (ref "E6") (pin "6") (pinfunction "I5_6") (pintype "input"))
      (node (ref "R23") (pin "8") (pinfunction "1_8") (pintype "passive"))
      (node (ref "S1") (pin "9") (pinfunction "9_9") (pintype "passive"))
    )
    (net (code "55") (name "Net-(E6A-I6)") (class "Default")
      (node (ref "E6") (pin "11") (pinfunction "I6_11") (pintype "input"))
      (node (ref "R23") (pin "2") (pinfunction "1_2") (pintype "passive"))
      (node (ref "S1") (pin "15") (pinfunction "15_15") (pintype "passive"))
    )
    (net (code "56") (name "Net-(E6A-I7)") (class "Default")
      (node (ref "E6") (pin "12") (pinfunction "I7_12") (pintype "input"))
      (node (ref "R23") (pin "1") (pinfunction "1_1") (pintype "passive"))
      (node (ref "S1") (pin "16") (pinfunction "16_16") (pintype "passive"))
    )
    (net (code "57") (name "Net-(Q1-B)") (class "Default")
      (node (ref "Q1") (pin "2") (pinfunction "B_2") (pintype "passive"))
      (node (ref "R10") (pin "2") (pinfunction "2_2") (pintype "passive"))
    )
    (net (code "58") (name "Net-(Q1-C)") (class "Default")
      (node (ref "Q1") (pin "3") (pinfunction "C_3") (pintype "passive"))
      (node (ref "R5") (pin "1") (pinfunction "1_1") (pintype "passive"))
    )
    (net (code "59") (name "Net-(Q2-B)") (class "Default")
      (node (ref "Q2") (pin "2") (pinfunction "B_2") (pintype "passive"))
      (node (ref "R11") (pin "2") (pinfunction "2_2") (pintype "passive"))
    )
    (net (code "60") (name "Net-(Q2-C)") (class "Default")
      (node (ref "Q2") (pin "3") (pinfunction "C_3") (pintype "passive"))
      (node (ref "R6") (pin "1") (pinfunction "1_1") (pintype "passive"))
    )
    (net (code "61") (name "Net-(Q3-B)") (class "Default")
      (node (ref "Q3") (pin "2") (pinfunction "B_2") (pintype "passive"))
      (node (ref "R24") (pin "2") (pinfunction "2_2") (pintype "passive"))
    )
    (net (code "62") (name "Net-(R3-Pad2)") (class "Default")
      (node (ref "R3") (pin "2") (pinfunction "2_2") (pintype "passive"))
      (node (ref "SW1") (pin "1") (pinfunction "1_1") (pintype "passive"))
    )
    (net (code "63") (name "Net-(SW1B-1)") (class "Default")
      (node (ref "R4") (pin "2") (pinfunction "2_2") (pintype "passive"))
      (node (ref "SW1") (pin "2") (pinfunction "1_2") (pintype "passive"))
    )
    (net (code "64") (name "Net-(SW1C-1)") (class "Default")
      (node (ref "R8") (pin "2") (pinfunction "2_2") (pintype "passive"))
      (node (ref "SW1") (pin "3") (pinfunction "1_3") (pintype "passive"))
    )
    (net (code "65") (name "Net-(SW1D-1)") (class "Default")
      (node (ref "R9") (pin "2") (pinfunction "2_2") (pintype "passive"))
      (node (ref "SW1") (pin "4") (pinfunction "1_4") (pintype "passive"))
    )
    (net (code "66") (name "Net-(SW2-S)") (class "Default")
      (node (ref "R12") (pin "2") (pinfunction "2_2") (pintype "passive"))
      (node (ref "SW2") (pin "1") (pinfunction "S_1") (pintype "passive"))
      (node (ref "SW2") (pin "2") (pinfunction "S1_2") (pintype "passive"))
    )
    (net (code "67") (name "Net-(U1-PB6(XTAL1{slash}TOSC1))") (class "Default")
      (node (ref "C9") (pin "1") (pinfunction "1_1") (pintype "passive"))
      (node (ref "R18") (pin "1") (pinfunction "1_1") (pintype "passive"))
      (node (ref "U1") (pin "9") (pinfunction "PB6(XTAL1/TOSC1)_9") (pintype "bidirectional"))
      (node (ref "Y1") (pin "2") (pinfunction "2_2") (pintype "passive"))
    )
    (net (code "68") (name "Net-(U1-PB7(XTAL2{slash}TOSC2))") (class "Default")
      (node (ref "C7") (pin "1") (pinfunction "1_1") (pintype "passive"))
      (node (ref "R18") (pin "2") (pinfunction "2_2") (pintype "passive"))
      (node (ref "U1") (pin "10") (pinfunction "PB7(XTAL2/TOSC2)_10") (pintype "bidirectional"))
      (node (ref "Y1") (pin "1") (pinfunction "1_1") (pintype "passive"))
    )
    (net (code "69") (name "Net-(U1-PD0(RXD))") (class "Default")
      (node (ref "R16") (pin "1") (pinfunction "1_1") (pintype "passive"))
      (node (ref "U1") (pin "2") (pinfunction "PD0(RXD)_2") (pintype "bidirectional"))
    )
    (net (code "70") (name "Net-(U1-PD1(TXD))") (class "Default")
      (node (ref "R17") (pin "1") (pinfunction "1_1") (pintype "passive"))
      (node (ref "U1") (pin "3") (pinfunction "PD1(TXD)_3") (pintype "bidirectional"))
    )
    (net (code "71") (name "Net-(U8A-O)") (class "Default")
      (node (ref "U8") (pin "12") (pinfunction "O_12") (pintype "output"))
      (node (ref "U8") (pin "3") (pinfunction "I0_3") (pintype "input"))
      (node (ref "U8") (pin "4") (pinfunction "I1_4") (pintype "input"))
      (node (ref "U8") (pin "5") (pinfunction "I2_5") (pintype "input"))
    )
    (net (code "72") (name "Net-(U8C-I0)") (class "Default")
      (node (ref "U8") (pin "9") (pinfunction "I0_9") (pintype "input"))
      (node (ref "U9") (pin "8") (pinfunction "O_8") (pintype "output"))
    )
    (net (code "73") (name "Net-(U8C-O)") (class "Default")
      (node (ref "U8") (pin "8") (pinfunction "O_8") (pintype "output"))
      (node (ref "U9") (pin "13") (pinfunction "I1_13") (pintype "input"))
      (node (ref "U9") (pin "2") (pinfunction "I1_2") (pintype "input"))
    )
    (net (code "74") (name "Net-(U9A-O)") (class "Default")
      (node (ref "U9") (pin "12") (pinfunction "I0_12") (pintype "input"))
      (node (ref "U9") (pin "3") (pinfunction "O_3") (pintype "output"))
    )
    (net (code "75") (name "Net-(U10A-C1+)") (class "Default")
      (node (ref "C14") (pin "1") (pinfunction "1_1") (pintype "passive"))
      (node (ref "U10") (pin "1") (pinfunction "C1+_1") (pintype "bidirectional"))
    )
    (net (code "76") (name "Net-(U10A-C1-)") (class "Default")
      (node (ref "C14") (pin "2") (pinfunction "2_2") (pintype "passive"))
      (node (ref "U10") (pin "3") (pinfunction "C1-_3") (pintype "bidirectional"))
    )
    (net (code "77") (name "Net-(U10A-C2+)") (class "Default")
      (node (ref "C15") (pin "1") (pinfunction "1_1") (pintype "passive"))
      (node (ref "U10") (pin "4") (pinfunction "C2+_4") (pintype "bidirectional"))
    )
    (net (code "78") (name "Net-(U10A-C2-)") (class "Default")
      (node (ref "C15") (pin "2") (pinfunction "2_2") (pintype "passive"))
      (node (ref "U10") (pin "5") (pinfunction "C2-_5") (pintype "bidirectional"))
    )
    (net (code "79") (name "Net-(U10A-V+)") (class "Default")
      (node (ref "C16") (pin "1") (pinfunction "1_1") (pintype "passive"))
      (node (ref "U10") (pin "2") (pinfunction "V+_2") (pintype "bidirectional"))
    )
    (net (code "80") (name "Net-(U10A-V-)") (class "Default")
      (node (ref "C17") (pin "2") (pinfunction "2_2") (pintype "passive"))
      (node (ref "U10") (pin "6") (pinfunction "V-_6") (pintype "bidirectional"))
    )
    (net (code "81") (name "POWER_OK") (class "Default")
      (node (ref "J1") (pin "BV2") (pinfunction "1_BV2") (pintype "bidirectional"))
      (node (ref "R24") (pin "1") (pinfunction "1_1") (pintype "passive"))
    )
    (net (code "82") (name "PROG") (class "Default")
      (node (ref "C11") (pin "2") (pinfunction "2_2") (pintype "passive"))
      (node (ref "J2") (pin "1") (pinfunction "1_1") (pintype "passive"))
      (node (ref "R20") (pin "2") (pinfunction "2_2") (pintype "passive"))
      (node (ref "U10") (pin "11") (pinfunction "T1IN_11") (pintype "input"))
      (node (ref "U10") (pin "12") (pinfunction "R1OUT_12") (pintype "output"))
    )
    (net (code "83") (name "PULSE_LA") (class "Default")
      (node (ref "J1") (pin "DR2") (pinfunction "1_DR2") (pintype "bidirectional"))
      (node (ref "Q2") (pin "1") (pinfunction "E_1") (pintype "passive"))
    )
    (net (code "84") (name "RETURN") (class "Default")
      (node (ref "J1") (pin "AR2") (pinfunction "1_AR2") (pintype "bidirectional"))
    )
    (net (code "85") (name "RXD") (class "Default")
      (node (ref "J2") (pin "2") (pinfunction "2_2") (pintype "passive"))
      (node (ref "R16") (pin "2") (pinfunction "2_2") (pintype "passive"))
      (node (ref "U10") (pin "9") (pinfunction "R2OUT_9") (pintype "output"))
    )
    (net (code "86") (name "RXD232") (class "Default")
      (node (ref "J4") (pin "J") (pinfunction "8_J") (pintype "bidirectional"))
      (node (ref "J5") (pin "2") (pinfunction "F_2") (pintype "passive"))
      (node (ref "U10") (pin "8") (pinfunction "R2IN_8") (pintype "input"))
    )
    (net (code "87") (name "R_RUN") (class "Default")
      (node (ref "R2") (pin "1") (pinfunction "1_1") (pintype "passive"))
      (node (ref "U1") (pin "14") (pinfunction "PB0(ICP)_14") (pintype "bidirectional"))
    )
    (net (code "88") (name "R_SW") (class "Default")
      (node (ref "C10") (pin "1") (pinfunction "1_1") (pintype "passive"))
      (node (ref "R1") (pin "1") (pinfunction "1_1") (pintype "passive"))
      (node (ref "R12") (pin "1") (pinfunction "1_1") (pintype "passive"))
      (node (ref "U1") (pin "15") (pinfunction "PB1(OC1A)_15") (pintype "bidirectional"))
    )
    (net (code "89") (name "SCL") (class "Default")
      (node (ref "R22") (pin "1") (pinfunction "1_1") (pintype "passive"))
      (node (ref "U1") (pin "28") (pinfunction "PC5(ADC5/SCL)_28") (pintype "bidirectional"))
      (node (ref "U11") (pin "6") (pinfunction "SCL_6") (pintype "input"))
      (node (ref "U2") (pin "12") (pinfunction "SCL_12") (pintype "input"))
    )
    (net (code "90") (name "SDA") (class "Default")
      (node (ref "R21") (pin "1") (pinfunction "1_1") (pintype "passive"))
      (node (ref "U1") (pin "27") (pinfunction "PC4(ADC4/SDA)_27") (pintype "bidirectional"))
      (node (ref "U11") (pin "5") (pinfunction "SDA_5") (pintype "bidirectional"))
      (node (ref "U2") (pin "13") (pinfunction "SDA_13") (pintype "bidirectional"))
    )
    (net (code "91") (name "SET_FF") (class "Default")
      (node (ref "U1") (pin "4") (pinfunction "PD2(INT0)_4") (pintype "bidirectional"))
      (node (ref "U9") (pin "1") (pinfunction "I0_1") (pintype "input"))
    )
    (net (code "92") (name "SHOW_DATA") (class "Default")
      (node (ref "U1") (pin "5") (pinfunction "PD3(INT1)_5") (pintype "bidirectional"))
      (node (ref "U8") (pin "1") (pinfunction "I0_1") (pintype "input"))
    )
    (net (code "93") (name "SOURCE") (class "Default")
      (node (ref "E8") (pin "6") (pinfunction "A5_6") (pintype "input"))
      (node (ref "J1") (pin "AL2") (pinfunction "1_AL2") (pintype "bidirectional"))
    )
    (net (code "94") (name "STROBE") (class "Default")
      (node (ref "J1") (pin "AM2") (pinfunction "1_AM2") (pintype "bidirectional"))
    )
    (net (code "95") (name "SW") (class "Default")
      (node (ref "J1") (pin "DV2") (pinfunction "1_DV2") (pintype "bidirectional"))
      (node (ref "R1") (pin "2") (pinfunction "2_2") (pintype "passive"))
    )
    (net (code "96") (name "TP1") (class "Default")
      (node (ref "J1") (pin "CD2") (pinfunction "1_CD2") (pintype "bidirectional"))
    )
    (net (code "97") (name "TP2") (class "Default")
      (node (ref "J1") (pin "CE2") (pinfunction "1_CE2") (pintype "bidirectional"))
    )
    (net (code "98") (name "TP3") (class "Default")
      (node (ref "J1") (pin "CH2") (pinfunction "1_CH2") (pintype "bidirectional"))
    )
    (net (code "99") (name "TP4") (class "Default")
      (node (ref "J1") (pin "CJ2") (pinfunction "1_CJ2") (pintype "bidirectional"))
      (node (ref "U9") (pin "4") (pinfunction "I0_4") (pintype "input"))
      (node (ref "U9") (pin "5") (pinfunction "I1_5") (pintype "input"))
    )
    (net (code "100") (name "TXD") (class "Default")
      (node (ref "J2") (pin "3") (pinfunction "3_3") (pintype "passive"))
      (node (ref "R17") (pin "2") (pinfunction "2_2") (pintype "passive"))
      (node (ref "U10") (pin "10") (pinfunction "T2IN_10") (pintype "input"))
    )
    (net (code "101") (name "TXD232") (class "Default")
      (node (ref "J4") (pin "F") (pinfunction "6_F") (pintype "bidirectional"))
      (node (ref "J5") (pin "3") (pinfunction "F_3") (pintype "passive"))
      (node (ref "U10") (pin "7") (pinfunction "T2OUT_7") (pintype "output"))
    )
    (net (code "102") (name "V+") (class "Default")
      (node (ref "C20") (pin "1") (pinfunction "1_1") (pintype "passive"))
      (node (ref "C21") (pin "1") (pinfunction "1_1") (pintype "passive"))
      (node (ref "D2") (pin "C") (pinfunction "C_C") (pintype "passive"))
      (node (ref "D3") (pin "C") (pinfunction "C_C") (pintype "passive"))
      (node (ref "E3") (pin "28") (pinfunction "VCC_28") (pintype "power_in"))
      (node (ref "E4") (pin "28") (pinfunction "VCC_28") (pintype "power_in"))
      (node (ref "R15") (pin "2") (pinfunction "2_2") (pintype "passive"))
    )
    (net (code "103") (name "VCC") (class "Default")
      (node (ref "C1") (pin "1") (pinfunction "1_1") (pintype "passive"))
      (node (ref "C12") (pin "1") (pinfunction "1_1") (pintype "passive"))
      (node (ref "C13") (pin "1") (pinfunction "1_1") (pintype "passive"))
      (node (ref "C16") (pin "2") (pinfunction "2_2") (pintype "passive"))
      (node (ref "C18") (pin "1") (pinfunction "1_1") (pintype "passive"))
      (node (ref "C19") (pin "1") (pinfunction "1_1") (pintype "passive"))
      (node (ref "C2") (pin "1") (pinfunction "1_1") (pintype "passive"))
      (node (ref "C23") (pin "1") (pinfunction "1_1") (pintype "passive"))
      (node (ref "C24") (pin "1") (pinfunction "1_1") (pintype "passive"))
      (node (ref "C25") (pin "1") (pinfunction "1_1") (pintype "passive"))
      (node (ref "C26") (pin "1") (pinfunction "1_1") (pintype "passive"))
      (node (ref "C27") (pin "1") (pinfunction "1_1") (pintype "passive"))
      (node (ref "C28") (pin "1") (pinfunction "1_1") (pintype "passive"))
      (node (ref "C29") (pin "1") (pinfunction "1_1") (pintype "passive"))
      (node (ref "C3") (pin "1") (pinfunction "1_1") (pintype "passive"))
      (node (ref "C30") (pin "+") (pinfunction "+_+") (pintype "passive"))
      (node (ref "C4") (pin "1") (pinfunction "1_1") (pintype "passive"))
      (node (ref "C5") (pin "1") (pinfunction "1_1") (pintype "passive"))
      (node (ref "C6") (pin "1") (pinfunction "1_1") (pintype "passive"))
      (node (ref "C8") (pin "1") (pinfunction "1_1") (pintype "passive"))
      (node (ref "D1") (pin "C") (pinfunction "C_C") (pintype "passive"))
      (node (ref "D3") (pin "A") (pinfunction "A_A") (pintype "passive"))
      (node (ref "E7") (pin "1") (pinfunction "I0_1") (pintype "input"))
      (node (ref "E7") (pin "12") (pinfunction "I2_12") (pintype "input"))
      (node (ref "E7") (pin "13") (pinfunction "I3_13") (pintype "input"))
      (node (ref "J1") (pin "AA2") (pinfunction "1_AA2") (pintype "bidirectional"))
      (node (ref "J1") (pin "BA2") (pinfunction "1_BA2") (pintype "bidirectional"))
      (node (ref "J1") (pin "CA2") (pinfunction "1_CA2") (pintype "bidirectional"))
      (node (ref "J3") (pin "2") (pinfunction "2_2") (pintype "passive"))
      (node (ref "R13") (pin "2") (pinfunction "2_2") (pintype "passive"))
      (node (ref "R14") (pin "2") (pinfunction "2_2") (pintype "passive"))
      (node (ref "R19") (pin "2") (pinfunction "2_2") (pintype "passive"))
      (node (ref "R21") (pin "2") (pinfunction "2_2") (pintype "passive"))
      (node (ref "R22") (pin "2") (pinfunction "2_2") (pintype "passive"))
      (node (ref "R23") (pin "10") (pinfunction "2_10") (pintype "passive"))
      (node (ref "R23") (pin "11") (pinfunction "2_11") (pintype "passive"))
      (node (ref "R23") (pin "12") (pinfunction "2_12") (pintype "passive"))
      (node (ref "R23") (pin "13") (pinfunction "2_13") (pintype "passive"))
      (node (ref "R23") (pin "14") (pinfunction "2_14") (pintype "passive"))
      (node (ref "R23") (pin "15") (pinfunction "2_15") (pintype "passive"))
      (node (ref "R23") (pin "16") (pinfunction "2_16") (pintype "passive"))
      (node (ref "R23") (pin "9") (pinfunction "2_9") (pintype "passive"))
      (node (ref "R25") (pin "1") (pinfunction "1_1") (pintype "passive"))
      (node (ref "R5") (pin "2") (pinfunction "2_2") (pintype "passive"))
      (node (ref "R6") (pin "2") (pinfunction "2_2") (pintype "passive"))
      (node (ref "U1") (pin "20") (pinfunction "AVCC_20") (pintype "power_in"))
      (node (ref "U1") (pin "21") (pinfunction "AREF_21") (pintype "passive"))
      (node (ref "U1") (pin "7") (pinfunction "VCC_7") (pintype "power_in"))
      (node (ref "U11") (pin "8") (pinfunction "VCC_8") (pintype "power_in"))
      (node (ref "U2") (pin "18") (pinfunction "~{RESET}_18") (pintype "input"))
      (node (ref "U2") (pin "9") (pinfunction "VDD_9") (pintype "power_in"))
      (node (ref "U7") (pin "12") (pinfunction "I0_12") (pintype "input"))
      (node (ref "U7") (pin "13") (pinfunction "I1_13") (pintype "input"))
    )
    (net (code "104") (name "WRITE") (class "Default")
      (node (ref "E8") (pin "4") (pinfunction "A3_4") (pintype "input"))
      (node (ref "J1") (pin "AS2") (pinfunction "1_AS2") (pintype "bidirectional"))
    )
    (net (code "105") (name "W_DATA_00") (class "Default")
      (node (ref "U2") (pin "7") (pinfunction "GPB6_7") (pintype "bidirectional"))
      (node (ref "U3") (pin "1") (pinfunction "I0_1") (pintype "input"))
    )
    (net (code "106") (name "W_DATA_01") (class "Default")
      (node (ref "U2") (pin "6") (pinfunction "GPB5_6") (pintype "bidirectional"))
      (node (ref "U3") (pin "4") (pinfunction "I0_4") (pintype "input"))
    )
    (net (code "107") (name "W_DATA_02") (class "Default")
      (node (ref "U2") (pin "5") (pinfunction "GPB4_5") (pintype "bidirectional"))
      (node (ref "U3") (pin "12") (pinfunction "I0_12") (pintype "input"))
    )
    (net (code "108") (name "W_DATA_03") (class "Default")
      (node (ref "U2") (pin "3") (pinfunction "GPB2_3") (pintype "bidirectional"))
      (node (ref "U3") (pin "9") (pinfunction "I0_9") (pintype "input"))
    )
    (net (code "109") (name "W_DATA_04") (class "Default")
      (node (ref "U2") (pin "2") (pinfunction "GPB1_2") (pintype "bidirectional"))
      (node (ref "U4") (pin "1") (pinfunction "I0_1") (pintype "input"))
    )
    (net (code "110") (name "W_DATA_05") (class "Default")
      (node (ref "U2") (pin "1") (pinfunction "GPB0_1") (pintype "bidirectional"))
      (node (ref "U4") (pin "4") (pinfunction "I0_4") (pintype "input"))
    )
    (net (code "111") (name "W_DATA_06") (class "Default")
      (node (ref "U2") (pin "27") (pinfunction "GPA6_27") (pintype "bidirectional"))
      (node (ref "U4") (pin "12") (pinfunction "I0_12") (pintype "input"))
    )
    (net (code "112") (name "W_DATA_07") (class "Default")
      (node (ref "U2") (pin "26") (pinfunction "GPA5_26") (pintype "bidirectional"))
      (node (ref "U4") (pin "9") (pinfunction "I0_9") (pintype "input"))
    )
    (net (code "113") (name "W_DATA_08") (class "Default")
      (node (ref "U2") (pin "25") (pinfunction "GPA4_25") (pintype "bidirectional"))
      (node (ref "U5") (pin "1") (pinfunction "I0_1") (pintype "input"))
    )
    (net (code "114") (name "W_DATA_09") (class "Default")
      (node (ref "U2") (pin "23") (pinfunction "GPA2_23") (pintype "bidirectional"))
      (node (ref "U5") (pin "4") (pinfunction "I0_4") (pintype "input"))
    )
    (net (code "115") (name "W_DATA_10") (class "Default")
      (node (ref "U2") (pin "22") (pinfunction "GPA1_22") (pintype "bidirectional"))
      (node (ref "U5") (pin "12") (pinfunction "I0_12") (pintype "input"))
    )
    (net (code "116") (name "W_DATA_11") (class "Default")
      (node (ref "U2") (pin "21") (pinfunction "GPA0_21") (pintype "bidirectional"))
      (node (ref "U5") (pin "9") (pinfunction "I0_9") (pintype "input"))
    )
    (net (code "117") (name "W_INITIALIZE") (class "Default")
      (node (ref "R10") (pin "1") (pinfunction "1_1") (pintype "passive"))
      (node (ref "R13") (pin "1") (pinfunction "1_1") (pintype "passive"))
      (node (ref "U1") (pin "23") (pinfunction "PC0(ADC0)_23") (pintype "bidirectional"))
    )
    (net (code "118") (name "W_PULSE_LA") (class "Default")
      (node (ref "R11") (pin "1") (pinfunction "1_1") (pintype "passive"))
      (node (ref "R14") (pin "1") (pinfunction "1_1") (pintype "passive"))
      (node (ref "U1") (pin "24") (pinfunction "PC1(ADC1)_24") (pintype "bidirectional"))
    )
    (net (code "119") (name "W_STOP") (class "Default")
      (node (ref "U1") (pin "26") (pinfunction "PC3(ADC3)_26") (pintype "bidirectional"))
      (node (ref "U7") (pin "10") (pinfunction "I1_10") (pintype "input"))
      (node (ref "U7") (pin "9") (pinfunction "I0_9") (pintype "input"))
    )
    (net (code "120") (name "unconnected-(E8A-Y8-Pad11)") (class "Default")
      (node (ref "E8") (pin "11") (pinfunction "Y8_11") (pintype "tri_state"))
    )
    (net (code "121") (name "unconnected-(J1A-1-PadAA1)") (class "Default")
      (node (ref "J1") (pin "AA1") (pinfunction "1_AA1") (pintype "bidirectional"))
    )
    (net (code "122") (name "unconnected-(J1AK-1-PadBA1)") (class "Default")
      (node (ref "J1") (pin "BA1") (pinfunction "1_BA1") (pintype "bidirectional"))
    )
    (net (code "123") (name "unconnected-(J1AM-1-PadBB1)") (class "Default")
      (node (ref "J1") (pin "BB1") (pinfunction "1_BB1") (pintype "bidirectional"))
    )
    (net (code "124") (name "unconnected-(J1BN-1-PadBS2)") (class "Default")
      (node (ref "J1") (pin "BS2") (pinfunction "1_BS2") (pintype "bidirectional"))
    )
    (net (code "125") (name "unconnected-(J1BU-1-PadCA1)") (class "Default")
      (node (ref "J1") (pin "CA1") (pinfunction "1_CA1") (pintype "bidirectional"))
    )
    (net (code "126") (name "unconnected-(J1BW-1-PadCB1)") (class "Default")
      (node (ref "J1") (pin "CB1") (pinfunction "1_CB1") (pintype "bidirectional"))
    )
    (net (code "127") (name "unconnected-(J1C-1-PadAB1)") (class "Default")
      (node (ref "J1") (pin "AB1") (pinfunction "1_AB1") (pintype "bidirectional"))
    )
    (net (code "128") (name "unconnected-(J1DE-1-PadDA1)") (class "Default")
      (node (ref "J1") (pin "DA1") (pinfunction "1_DA1") (pintype "bidirectional"))
    )
    (net (code "129") (name "unconnected-(J1DG-1-PadDB1)") (class "Default")
      (node (ref "J1") (pin "DB1") (pinfunction "1_DB1") (pintype "bidirectional"))
    )
    (net (code "130") (name "unconnected-(J4-3-PadC)") (class "Default")
      (node (ref "J4") (pin "C") (pinfunction "3_C") (pintype "bidirectional"))
    )
    (net (code "131") (name "unconnected-(J4-4-PadD)") (class "Default")
      (node (ref "J4") (pin "D") (pinfunction "4_D") (pintype "bidirectional"))
    )
    (net (code "132") (name "unconnected-(J4-5-PadE)") (class "Default")
      (node (ref "J4") (pin "E") (pinfunction "5_E") (pintype "bidirectional"))
    )
    (net (code "133") (name "unconnected-(J4-7-PadH)") (class "Default")
      (node (ref "J4") (pin "H") (pinfunction "7_H") (pintype "bidirectional"))
    )
    (net (code "134") (name "unconnected-(J4-9-PadK)") (class "Default")
      (node (ref "J4") (pin "K") (pinfunction "9_K") (pintype "bidirectional"))
    )
    (net (code "135") (name "unconnected-(J4-10-PadL)") (class "Default")
      (node (ref "J4") (pin "L") (pinfunction "10_L") (pintype "bidirectional"))
    )
    (net (code "136") (name "unconnected-(J4-11-PadM)") (class "Default")
      (node (ref "J4") (pin "M") (pinfunction "11_M") (pintype "bidirectional"))
    )
    (net (code "137") (name "unconnected-(J4-12-PadN)") (class "Default")
      (node (ref "J4") (pin "N") (pinfunction "12_N") (pintype "bidirectional"))
    )
    (net (code "138") (name "unconnected-(J4-13-PadP)") (class "Default")
      (node (ref "J4") (pin "P") (pinfunction "13_P") (pintype "bidirectional"))
    )
    (net (code "139") (name "unconnected-(J4-14-PadR)") (class "Default")
      (node (ref "J4") (pin "R") (pinfunction "14_R") (pintype "bidirectional"))
    )
    (net (code "140") (name "unconnected-(J4-15-PadS)") (class "Default")
      (node (ref "J4") (pin "S") (pinfunction "15_S") (pintype "bidirectional"))
    )
    (net (code "141") (name "unconnected-(J4-16-PadT)") (class "Default")
      (node (ref "J4") (pin "T") (pinfunction "16_T") (pintype "bidirectional"))
    )
    (net (code "142") (name "unconnected-(J4-17-PadU)") (class "Default")
      (node (ref "J4") (pin "U") (pinfunction "17_U") (pintype "bidirectional"))
    )
    (net (code "143") (name "unconnected-(J4-18-PadV)") (class "Default")
      (node (ref "J4") (pin "V") (pinfunction "18_V") (pintype "bidirectional"))
    )
    (net (code "144") (name "unconnected-(J4-19-PadW)") (class "Default")
      (node (ref "J4") (pin "W") (pinfunction "19_W") (pintype "bidirectional"))
    )
    (net (code "145") (name "unconnected-(J4-20-PadX)") (class "Default")
      (node (ref "J4") (pin "X") (pinfunction "20_X") (pintype "bidirectional"))
    )
    (net (code "146") (name "unconnected-(J4-21-PadY)") (class "Default")
      (node (ref "J4") (pin "Y") (pinfunction "21_Y") (pintype "bidirectional"))
    )
    (net (code "147") (name "unconnected-(J4-23-PadAA)") (class "Default")
      (node (ref "J4") (pin "AA") (pinfunction "23_AA") (pintype "bidirectional"))
    )
    (net (code "148") (name "unconnected-(J4-24-PadBB)") (class "Default")
      (node (ref "J4") (pin "BB") (pinfunction "24_BB") (pintype "bidirectional"))
    )
    (net (code "149") (name "unconnected-(J4-25-PadCC)") (class "Default")
      (node (ref "J4") (pin "CC") (pinfunction "25_CC") (pintype "bidirectional"))
    )
    (net (code "150") (name "unconnected-(J4-26-PadDD)") (class "Default")
      (node (ref "J4") (pin "DD") (pinfunction "26_DD") (pintype "bidirectional"))
    )
    (net (code "151") (name "unconnected-(J4-27-PadEE)") (class "Default")
      (node (ref "J4") (pin "EE") (pinfunction "27_EE") (pintype "bidirectional"))
    )
    (net (code "152") (name "unconnected-(J4-28-PadFF)") (class "Default")
      (node (ref "J4") (pin "FF") (pinfunction "28_FF") (pintype "bidirectional"))
    )
    (net (code "153") (name "unconnected-(J4-29-PadHH)") (class "Default")
      (node (ref "J4") (pin "HH") (pinfunction "29_HH") (pintype "bidirectional"))
    )
    (net (code "154") (name "unconnected-(J4-30-PadJJ)") (class "Default")
      (node (ref "J4") (pin "JJ") (pinfunction "30_JJ") (pintype "bidirectional"))
    )
    (net (code "155") (name "unconnected-(J4-31-PadKK)") (class "Default")
      (node (ref "J4") (pin "KK") (pinfunction "31_KK") (pintype "bidirectional"))
    )
    (net (code "156") (name "unconnected-(J4-32-PadLL)") (class "Default")
      (node (ref "J4") (pin "LL") (pinfunction "32_LL") (pintype "bidirectional"))
    )
    (net (code "157") (name "unconnected-(J4-33-PadMM)") (class "Default")
      (node (ref "J4") (pin "MM") (pinfunction "33_MM") (pintype "bidirectional"))
    )
    (net (code "158") (name "unconnected-(J4-34-PadNN)") (class "Default")
      (node (ref "J4") (pin "NN") (pinfunction "34_NN") (pintype "bidirectional"))
    )
    (net (code "159") (name "unconnected-(J4-35-PadPP)") (class "Default")
      (node (ref "J4") (pin "PP") (pinfunction "35_PP") (pintype "bidirectional"))
    )
    (net (code "160") (name "unconnected-(J4-36-PadRR)") (class "Default")
      (node (ref "J4") (pin "RR") (pinfunction "36_RR") (pintype "bidirectional"))
    )
    (net (code "161") (name "unconnected-(U2-GPA3-Pad24)") (class "Default")
      (node (ref "U2") (pin "24") (pinfunction "GPA3_24") (pintype "bidirectional"))
    )
    (net (code "162") (name "unconnected-(U2-GPA7-Pad28)") (class "Default")
      (node (ref "U2") (pin "28") (pinfunction "GPA7_28") (pintype "bidirectional"))
    )
    (net (code "163") (name "unconnected-(U2-GPB3-Pad4)") (class "Default")
      (node (ref "U2") (pin "4") (pinfunction "GPB3_4") (pintype "bidirectional"))
    )
    (net (code "164") (name "unconnected-(U2-GPB7-Pad8)") (class "Default")
      (node (ref "U2") (pin "8") (pinfunction "GPB7_8") (pintype "bidirectional"))
    )
    (net (code "165") (name "unconnected-(U2-INTA-Pad20)") (class "Default")
      (node (ref "U2") (pin "20") (pinfunction "INTA_20") (pintype "output"))
    )
    (net (code "166") (name "unconnected-(U2-INTB-Pad19)") (class "Default")
      (node (ref "U2") (pin "19") (pinfunction "INTB_19") (pintype "output"))
    )
    (net (code "167") (name "unconnected-(U7D-O-Pad11)") (class "Default")
      (node (ref "U7") (pin "11") (pinfunction "O_11") (pintype "open_collector"))
    )
    (net (code "168") (name "unconnected-(U10A-T1OUT-Pad14)") (class "Default")
      (node (ref "U10") (pin "14") (pinfunction "T1OUT_14") (pintype "output"))
    )
    (net (code "169") (name "~{BMD_DIR}") (class "Default")
      (node (ref "E7") (pin "2") (pinfunction "I1_2") (pintype "input"))
      (node (ref "E8") (pin "17") (pinfunction "Y2_17") (pintype "tri_state"))
    )
    (net (code "170") (name "~{BREAK_CYCLE}") (class "Default")
      (node (ref "J1") (pin "BL2") (pinfunction "1_BL2") (pintype "bidirectional"))
    )
    (net (code "171") (name "~{BRK_DATA}") (class "Default")
      (node (ref "J1") (pin "BK2") (pinfunction "1_BK2") (pintype "bidirectional"))
      (node (ref "U7") (pin "3") (pinfunction "O_3") (pintype "open_collector"))
    )
    (net (code "172") (name "~{BRK_IN_PROG}") (class "Default")
      (node (ref "J1") (pin "BE2") (pinfunction "1_BE2") (pintype "bidirectional"))
    )
    (net (code "173") (name "~{BUS_STROBE}") (class "Default")
      (node (ref "J1") (pin "CK1") (pinfunction "1_CK1") (pintype "bidirectional"))
    )
    (net (code "174") (name "~{C0}") (class "Default")
      (node (ref "J1") (pin "CE1") (pinfunction "1_CE1") (pintype "bidirectional"))
    )
    (net (code "175") (name "~{C1}") (class "Default")
      (node (ref "J1") (pin "CH1") (pinfunction "1_CH1") (pintype "bidirectional"))
    )
    (net (code "176") (name "~{C2}") (class "Default")
      (node (ref "J1") (pin "CJ1") (pinfunction "1_CJ1") (pintype "bidirectional"))
    )
    (net (code "177") (name "~{CE}") (class "Default")
      (node (ref "C22") (pin "1") (pinfunction "1_1") (pintype "passive"))
      (node (ref "E3") (pin "20") (pinfunction "~{CE}_20") (pintype "input"))
      (node (ref "E4") (pin "20") (pinfunction "~{CE}_20") (pintype "input"))
      (node (ref "Q3") (pin "1") (pinfunction "C_1") (pintype "passive"))
      (node (ref "R15") (pin "1") (pinfunction "1_1") (pintype "passive"))
    )
    (net (code "178") (name "~{CPMA_DISABLE}") (class "Default")
      (node (ref "J1") (pin "CU1") (pinfunction "1_CU1") (pintype "bidirectional"))
    )
    (net (code "179") (name "~{DATA00}") (class "Default")
      (node (ref "J1") (pin "AR1") (pinfunction "1_AR1") (pintype "bidirectional"))
      (node (ref "U3") (pin "3") (pinfunction "O_3") (pintype "open_collector"))
    )
    (net (code "180") (name "~{DATA01}") (class "Default")
      (node (ref "J1") (pin "AS1") (pinfunction "1_AS1") (pintype "bidirectional"))
      (node (ref "U3") (pin "6") (pinfunction "O_6") (pintype "open_collector"))
    )
    (net (code "181") (name "~{DATA02}") (class "Default")
      (node (ref "J1") (pin "AU1") (pinfunction "1_AU1") (pintype "bidirectional"))
      (node (ref "U3") (pin "11") (pinfunction "O_11") (pintype "open_collector"))
    )
    (net (code "182") (name "~{DATA03}") (class "Default")
      (node (ref "J1") (pin "AV1") (pinfunction "1_AV1") (pintype "bidirectional"))
      (node (ref "U3") (pin "8") (pinfunction "O_8") (pintype "open_collector"))
    )
    (net (code "183") (name "~{DATA04}") (class "Default")
      (node (ref "J1") (pin "BR1") (pinfunction "1_BR1") (pintype "bidirectional"))
      (node (ref "U4") (pin "3") (pinfunction "O_3") (pintype "open_collector"))
    )
    (net (code "184") (name "~{DATA05}") (class "Default")
      (node (ref "J1") (pin "BS1") (pinfunction "1_BS1") (pintype "bidirectional"))
      (node (ref "U4") (pin "6") (pinfunction "O_6") (pintype "open_collector"))
    )
    (net (code "185") (name "~{DATA06}") (class "Default")
      (node (ref "J1") (pin "BU1") (pinfunction "1_BU1") (pintype "bidirectional"))
      (node (ref "U4") (pin "11") (pinfunction "O_11") (pintype "open_collector"))
    )
    (net (code "186") (name "~{DATA07}") (class "Default")
      (node (ref "J1") (pin "BV1") (pinfunction "1_BV1") (pintype "bidirectional"))
      (node (ref "U4") (pin "8") (pinfunction "O_8") (pintype "open_collector"))
    )
    (net (code "187") (name "~{DATA08}") (class "Default")
      (node (ref "J1") (pin "DR1") (pinfunction "1_DR1") (pintype "bidirectional"))
      (node (ref "U5") (pin "3") (pinfunction "O_3") (pintype "open_collector"))
    )
    (net (code "188") (name "~{DATA09}") (class "Default")
      (node (ref "J1") (pin "DS1") (pinfunction "1_DS1") (pintype "bidirectional"))
      (node (ref "U5") (pin "6") (pinfunction "O_6") (pintype "open_collector"))
    )
    (net (code "189") (name "~{DATA10}") (class "Default")
      (node (ref "J1") (pin "DU1") (pinfunction "1_DU1") (pintype "bidirectional"))
      (node (ref "U5") (pin "11") (pinfunction "O_11") (pintype "open_collector"))
    )
    (net (code "190") (name "~{DATA11}") (class "Default")
      (node (ref "J1") (pin "DV1") (pinfunction "1_DV1") (pintype "bidirectional"))
      (node (ref "U5") (pin "8") (pinfunction "O_8") (pintype "open_collector"))
    )
    (net (code "191") (name "~{DISABLE}") (class "Default")
      (node (ref "E7") (pin "10") (pinfunction "I1_10") (pintype "input"))
      (node (ref "E8") (pin "18") (pinfunction "Y1_18") (pintype "tri_state"))
    )
    (net (code "192") (name "~{D}") (class "Default")
      (node (ref "J1") (pin "DK2") (pinfunction "1_DK2") (pintype "bidirectional"))
    )
    (net (code "193") (name "~{EMA0}") (class "Default")
      (node (ref "E3") (pin "8") (pinfunction "A2_8") (pintype "input"))
      (node (ref "E4") (pin "8") (pinfunction "A2_8") (pintype "input"))
      (node (ref "E5") (pin "3") (pinfunction "C_3") (pintype "input"))
      (node (ref "J1") (pin "AD2") (pinfunction "1_AD2") (pintype "bidirectional"))
    )
    (net (code "194") (name "~{EMA1}") (class "Default")
      (node (ref "E3") (pin "9") (pinfunction "A1_9") (pintype "input"))
      (node (ref "E4") (pin "9") (pinfunction "A1_9") (pintype "input"))
      (node (ref "E5") (pin "2") (pinfunction "B_2") (pintype "input"))
      (node (ref "J1") (pin "AE2") (pinfunction "1_AE2") (pintype "bidirectional"))
    )
    (net (code "195") (name "~{EMA2}") (class "Default")
      (node (ref "E3") (pin "10") (pinfunction "A0_10") (pintype "input"))
      (node (ref "E4") (pin "10") (pinfunction "A0_10") (pintype "input"))
      (node (ref "E5") (pin "1") (pinfunction "A_1") (pintype "input"))
      (node (ref "J1") (pin "AH2") (pinfunction "1_AH2") (pintype "bidirectional"))
    )
    (net (code "196") (name "~{E}") (class "Default")
      (node (ref "J1") (pin "DL2") (pinfunction "1_DL2") (pintype "bidirectional"))
    )
    (net (code "197") (name "~{FSET}") (class "Default")
      (node (ref "J1") (pin "DP2") (pinfunction "1_DP2") (pintype "bidirectional"))
    )
    (net (code "198") (name "~{F}") (class "Default")
      (node (ref "J1") (pin "DJ2") (pinfunction "1_DJ2") (pintype "bidirectional"))
    )
    (net (code "199") (name "~{IND1}") (class "Default")
      (node (ref "J1") (pin "CU2") (pinfunction "1_CU2") (pintype "bidirectional"))
    )
    (net (code "200") (name "~{IND2}") (class "Default")
      (node (ref "J1") (pin "CV2") (pinfunction "1_CV2") (pintype "bidirectional"))
    )
    (net (code "201") (name "~{INTERNAL_IO}") (class "Default")
      (node (ref "J1") (pin "CL1") (pinfunction "1_CL1") (pintype "bidirectional"))
    )
    (net (code "202") (name "~{INT_RQST}") (class "Default")
      (node (ref "J1") (pin "CP1") (pinfunction "1_CP1") (pintype "bidirectional"))
    )
    (net (code "203") (name "~{IO_PAUSE}") (class "Default")
      (node (ref "J1") (pin "CD1") (pinfunction "1_CD1") (pintype "bidirectional"))
    )
    (net (code "204") (name "~{IR0}") (class "Default")
      (node (ref "J1") (pin "DD2") (pinfunction "1_DD2") (pintype "bidirectional"))
    )
    (net (code "205") (name "~{IR1}") (class "Default")
      (node (ref "J1") (pin "DE2") (pinfunction "1_DE2") (pintype "bidirectional"))
    )
    (net (code "206") (name "~{IR2}") (class "Default")
      (node (ref "J1") (pin "DH2") (pinfunction "1_DH2") (pintype "bidirectional"))
    )
    (net (code "207") (name "~{KEY_CONT}") (class "Default")
      (node (ref "J1") (pin "DU2") (pinfunction "1_DU2") (pintype "bidirectional"))
      (node (ref "U6") (pin "11") (pinfunction "O_11") (pintype "open_collector"))
    )
    (net (code "208") (name "~{LA_ENABLE}") (class "Default")
      (node (ref "J1") (pin "BM2") (pinfunction "1_BM2") (pintype "bidirectional"))
      (node (ref "U6") (pin "6") (pinfunction "O_6") (pintype "open_collector"))
    )
    (net (code "209") (name "~{LINK_DATA}") (class "Default")
      (node (ref "J1") (pin "CR2") (pinfunction "1_CR2") (pintype "bidirectional"))
    )
    (net (code "210") (name "~{LINK_LOAD}") (class "Default")
      (node (ref "J1") (pin "CS2") (pinfunction "1_CS2") (pintype "bidirectional"))
    )
    (net (code "211") (name "~{LINK}") (class "Default")
      (node (ref "J1") (pin "AV2") (pinfunction "1_AV2") (pintype "bidirectional"))
    )
    (net (code "212") (name "~{LOAD_CONT}") (class "Default")
      (node (ref "J1") (pin "BH2") (pinfunction "1_BH2") (pintype "bidirectional"))
    )
    (net (code "213") (name "~{MA00}") (class "Default")
      (node (ref "E3") (pin "21") (pinfunction "A10_21") (pintype "input"))
      (node (ref "E4") (pin "21") (pinfunction "A10_21") (pintype "input"))
      (node (ref "J1") (pin "AD1") (pinfunction "1_AD1") (pintype "bidirectional"))
    )
    (net (code "214") (name "~{MA01}") (class "Default")
      (node (ref "E3") (pin "23") (pinfunction "A11_23") (pintype "input"))
      (node (ref "E4") (pin "23") (pinfunction "A11_23") (pintype "input"))
      (node (ref "J1") (pin "AE1") (pinfunction "1_AE1") (pintype "bidirectional"))
    )
    (net (code "215") (name "~{MA02}") (class "Default")
      (node (ref "E3") (pin "24") (pinfunction "A9_24") (pintype "input"))
      (node (ref "E4") (pin "24") (pinfunction "A9_24") (pintype "input"))
      (node (ref "J1") (pin "AH1") (pinfunction "1_AH1") (pintype "bidirectional"))
    )
    (net (code "216") (name "~{MA03}") (class "Default")
      (node (ref "E3") (pin "25") (pinfunction "A8_25") (pintype "input"))
      (node (ref "E4") (pin "25") (pinfunction "A8_25") (pintype "input"))
      (node (ref "J1") (pin "AJ1") (pinfunction "1_AJ1") (pintype "bidirectional"))
    )
    (net (code "217") (name "~{MA04}") (class "Default")
      (node (ref "E3") (pin "26") (pinfunction "A13_26") (pintype "input"))
      (node (ref "E4") (pin "26") (pinfunction "A13_26") (pintype "input"))
      (node (ref "J1") (pin "BD1") (pinfunction "1_BD1") (pintype "bidirectional"))
    )
    (net (code "218") (name "~{MA05}") (class "Default")
      (node (ref "E3") (pin "1") (pinfunction "A14_1") (pintype "input"))
      (node (ref "E4") (pin "1") (pinfunction "A14_1") (pintype "input"))
      (node (ref "J1") (pin "BE1") (pinfunction "1_BE1") (pintype "bidirectional"))
    )
    (net (code "219") (name "~{MA06}") (class "Default")
      (node (ref "E3") (pin "2") (pinfunction "A12_2") (pintype "input"))
      (node (ref "E4") (pin "2") (pinfunction "A12_2") (pintype "input"))
      (node (ref "J1") (pin "BH1") (pinfunction "1_BH1") (pintype "bidirectional"))
    )
    (net (code "220") (name "~{MA07}") (class "Default")
      (node (ref "E3") (pin "3") (pinfunction "A7_3") (pintype "input"))
      (node (ref "E4") (pin "3") (pinfunction "A7_3") (pintype "input"))
      (node (ref "J1") (pin "BJ1") (pinfunction "1_BJ1") (pintype "bidirectional"))
    )
    (net (code "221") (name "~{MA08}") (class "Default")
      (node (ref "E3") (pin "4") (pinfunction "A6_4") (pintype "input"))
      (node (ref "E4") (pin "4") (pinfunction "A6_4") (pintype "input"))
      (node (ref "J1") (pin "DD1") (pinfunction "1_DD1") (pintype "bidirectional"))
    )
    (net (code "222") (name "~{MA09}") (class "Default")
      (node (ref "E3") (pin "5") (pinfunction "A5_5") (pintype "input"))
      (node (ref "E4") (pin "5") (pinfunction "A5_5") (pintype "input"))
      (node (ref "J1") (pin "DE1") (pinfunction "1_DE1") (pintype "bidirectional"))
    )
    (net (code "223") (name "~{MA10}") (class "Default")
      (node (ref "E3") (pin "6") (pinfunction "A4_6") (pintype "input"))
      (node (ref "E4") (pin "6") (pinfunction "A4_6") (pintype "input"))
      (node (ref "J1") (pin "DH1") (pinfunction "1_DH1") (pintype "bidirectional"))
    )
    (net (code "224") (name "~{MA11}") (class "Default")
      (node (ref "E3") (pin "7") (pinfunction "A3_7") (pintype "input"))
      (node (ref "E4") (pin "7") (pinfunction "A3_7") (pintype "input"))
      (node (ref "J1") (pin "DJ1") (pinfunction "1_DJ1") (pintype "bidirectional"))
    )
    (net (code "225") (name "~{MD00}") (class "Default")
      (node (ref "E1") (pin "2") (pinfunction "A1_2") (pintype "bidirectional"))
      (node (ref "J1") (pin "AK1") (pinfunction "1_AK1") (pintype "bidirectional"))
    )
    (net (code "226") (name "~{MD01}") (class "Default")
      (node (ref "E1") (pin "3") (pinfunction "A2_3") (pintype "bidirectional"))
      (node (ref "J1") (pin "AL1") (pinfunction "1_AL1") (pintype "bidirectional"))
    )
    (net (code "227") (name "~{MD02}") (class "Default")
      (node (ref "E1") (pin "4") (pinfunction "A3_4") (pintype "bidirectional"))
      (node (ref "J1") (pin "AM1") (pinfunction "1_AM1") (pintype "bidirectional"))
    )
    (net (code "228") (name "~{MD03}") (class "Default")
      (node (ref "E1") (pin "5") (pinfunction "A4_5") (pintype "bidirectional"))
      (node (ref "J1") (pin "AP1") (pinfunction "1_AP1") (pintype "bidirectional"))
    )
    (net (code "229") (name "~{MD04}") (class "Default")
      (node (ref "E2") (pin "2") (pinfunction "A1_2") (pintype "bidirectional"))
      (node (ref "J1") (pin "BK1") (pinfunction "1_BK1") (pintype "bidirectional"))
    )
    (net (code "230") (name "~{MD05}") (class "Default")
      (node (ref "E2") (pin "3") (pinfunction "A2_3") (pintype "bidirectional"))
      (node (ref "J1") (pin "BL1") (pinfunction "1_BL1") (pintype "bidirectional"))
    )
    (net (code "231") (name "~{MD06}") (class "Default")
      (node (ref "E2") (pin "4") (pinfunction "A3_4") (pintype "bidirectional"))
      (node (ref "J1") (pin "BM1") (pinfunction "1_BM1") (pintype "bidirectional"))
    )
    (net (code "232") (name "~{MD07}") (class "Default")
      (node (ref "E2") (pin "5") (pinfunction "A4_5") (pintype "bidirectional"))
      (node (ref "J1") (pin "BP1") (pinfunction "1_BP1") (pintype "bidirectional"))
    )
    (net (code "233") (name "~{MD08}") (class "Default")
      (node (ref "E2") (pin "6") (pinfunction "A5_6") (pintype "bidirectional"))
      (node (ref "J1") (pin "DK1") (pinfunction "1_DK1") (pintype "bidirectional"))
    )
    (net (code "234") (name "~{MD09}") (class "Default")
      (node (ref "E2") (pin "7") (pinfunction "A6_7") (pintype "bidirectional"))
      (node (ref "J1") (pin "DL1") (pinfunction "1_DL1") (pintype "bidirectional"))
    )
    (net (code "235") (name "~{MD10}") (class "Default")
      (node (ref "E2") (pin "8") (pinfunction "A7_8") (pintype "bidirectional"))
      (node (ref "J1") (pin "DM1") (pinfunction "1_DM1") (pintype "bidirectional"))
    )
    (net (code "236") (name "~{MD11}") (class "Default")
      (node (ref "E2") (pin "9") (pinfunction "A8_9") (pintype "bidirectional"))
      (node (ref "J1") (pin "DP1") (pinfunction "1_DP1") (pintype "bidirectional"))
    )
    (net (code "237") (name "~{MD_DIR}") (class "Default")
      (node (ref "E8") (pin "8") (pinfunction "A7_8") (pintype "input"))
      (node (ref "J1") (pin "AK2") (pinfunction "1_AK2") (pintype "bidirectional"))
      (node (ref "U7") (pin "6") (pinfunction "O_6") (pintype "open_collector"))
    )
    (net (code "238") (name "~{MEM_START}") (class "Default")
      (node (ref "J1") (pin "AJ2") (pinfunction "1_AJ2") (pintype "bidirectional"))
      (node (ref "U6") (pin "3") (pinfunction "O_3") (pintype "open_collector"))
    )
    (net (code "239") (name "~{MS_DISABLE}") (class "Default")
      (node (ref "J1") (pin "CV1") (pinfunction "1_CV1") (pintype "bidirectional"))
      (node (ref "U6") (pin "8") (pinfunction "O_8") (pintype "open_collector"))
    )
    (net (code "240") (name "~{NOT_LAST_TR}") (class "Default")
      (node (ref "J1") (pin "CM1") (pinfunction "1_CM1") (pintype "bidirectional"))
    )
    (net (code "241") (name "~{NTS_STALL}") (class "Default")
      (node (ref "J1") (pin "BR2") (pinfunction "1_BR2") (pintype "bidirectional"))
    )
    (net (code "242") (name "~{OVERFLOW}") (class "Default")
      (node (ref "J1") (pin "BJ2") (pinfunction "1_BJ2") (pintype "bidirectional"))
    )
    (net (code "243") (name "~{READ_EN}") (class "Default")
      (node (ref "E1") (pin "1") (pinfunction "DIR_1") (pintype "input"))
      (node (ref "E2") (pin "1") (pinfunction "DIR_1") (pintype "input"))
      (node (ref "E3") (pin "22") (pinfunction "~{OE}_22") (pintype "input"))
      (node (ref "E4") (pin "22") (pinfunction "~{OE}_22") (pintype "input"))
      (node (ref "E7") (pin "8") (pinfunction "O_8") (pintype "output"))
    )
    (net (code "244") (name "~{RESET}") (class "Default")
      (node (ref "C11") (pin "1") (pinfunction "1_1") (pintype "passive"))
      (node (ref "D1") (pin "A") (pinfunction "A_A") (pintype "passive"))
      (node (ref "J3") (pin "5") (pinfunction "5_5") (pintype "passive"))
      (node (ref "R19") (pin "1") (pinfunction "1_1") (pintype "passive"))
      (node (ref "U1") (pin "1") (pinfunction "PC6(/RESET)_1") (pintype "bidirectional"))
    )
    (net (code "245") (name "~{ROM_ADDR}") (class "Default")
      (node (ref "E5") (pin "6") (pinfunction "G1_6") (pintype "input"))
      (node (ref "J1") (pin "AU2") (pinfunction "1_AU2") (pintype "bidirectional"))
    )
    (net (code "246") (name "~{RUN}") (class "Default")
      (node (ref "J1") (pin "BU2") (pinfunction "1_BU2") (pintype "bidirectional"))
      (node (ref "R2") (pin "2") (pinfunction "2_2") (pintype "passive"))
    )
    (net (code "247") (name "~{SKIP}") (class "Default")
      (node (ref "J1") (pin "CS1") (pinfunction "1_CS1") (pintype "bidirectional"))
    )
    (net (code "248") (name "~{SOURCE}") (class "Default")
      (node (ref "E8") (pin "14") (pinfunction "Y5_14") (pintype "tri_state"))
      (node (ref "E8") (pin "7") (pinfunction "A6_7") (pintype "input"))
    )
    (net (code "249") (name "~{STOP}") (class "Default")
      (node (ref "J1") (pin "DS2") (pinfunction "1_DS2") (pintype "bidirectional"))
      (node (ref "U7") (pin "8") (pinfunction "O_8") (pintype "open_collector"))
    )
    (net (code "250") (name "~{TP4}") (class "Default")
      (node (ref "U8") (pin "10") (pinfunction "I1_10") (pintype "input"))
      (node (ref "U9") (pin "6") (pinfunction "O_6") (pintype "output"))
    )
    (net (code "251") (name "~{TS1}") (class "Default")
      (node (ref "J1") (pin "CK2") (pinfunction "1_CK2") (pintype "bidirectional"))
    )
    (net (code "252") (name "~{TS2}") (class "Default")
      (node (ref "J1") (pin "CL2") (pinfunction "1_CL2") (pintype "bidirectional"))
    )
    (net (code "253") (name "~{TS3}") (class "Default")
      (node (ref "J1") (pin "CM2") (pinfunction "1_CM2") (pintype "bidirectional"))
    )
    (net (code "254") (name "~{TS4}") (class "Default")
      (node (ref "J1") (pin "CP2") (pinfunction "1_CP2") (pintype "bidirectional"))
      (node (ref "U8") (pin "13") (pinfunction "I2_13") (pintype "input"))
    )
    (net (code "255") (name "~{USER_MODE}") (class "Default")
      (node (ref "J1") (pin "DM2") (pinfunction "1_DM2") (pintype "bidirectional"))
    )
    (net (code "256") (name "~{WRITE_EN}") (class "Default")
      (node (ref "E3") (pin "27") (pinfunction "~{WE}_27") (pintype "input"))
      (node (ref "E4") (pin "27") (pinfunction "~{WE}_27") (pintype "input"))
      (node (ref "E7") (pin "6") (pinfunction "O_6") (pintype "output"))
    )
    (net (code "257") (name "~{WRITE}") (class "Default")
      (node (ref "E8") (pin "16") (pinfunction "Y3_16") (pintype "tri_state"))
      (node (ref "E8") (pin "5") (pinfunction "A4_5") (pintype "input"))
    )
    (net (code "258") (name "~{W_KEY_CONTROL}") (class "Default")
      (node (ref "U1") (pin "13") (pinfunction "PD7(AIN1)_13") (pintype "bidirectional"))
      (node (ref "U6") (pin "12") (pinfunction "I0_12") (pintype "input"))
    )
    (net (code "259") (name "~{W_LA_ENABLE}") (class "Default")
      (node (ref "U1") (pin "11") (pinfunction "PD5(T1)_11") (pintype "bidirectional"))
      (node (ref "U6") (pin "4") (pinfunction "I0_4") (pintype "input"))
    )
    (net (code "260") (name "~{W_MEM_START}") (class "Default")
      (node (ref "R7") (pin "2") (pinfunction "2_2") (pintype "passive"))
      (node (ref "U1") (pin "25") (pinfunction "PC2(ADC2)_25") (pintype "bidirectional"))
      (node (ref "U6") (pin "1") (pinfunction "I0_1") (pintype "input"))
      (node (ref "U6") (pin "2") (pinfunction "I1_2") (pintype "input"))
    )
    (net (code "261") (name "~{W_MS_IR_DISABLE}") (class "Default")
      (node (ref "U1") (pin "12") (pinfunction "PD6(AIN0)_12") (pintype "bidirectional"))
      (node (ref "U6") (pin "9") (pinfunction "I0_9") (pintype "input"))
    )
  )
)
